# User_IO_Buffers.net
KiCad netlist of a schematic drawn in Altium Designer
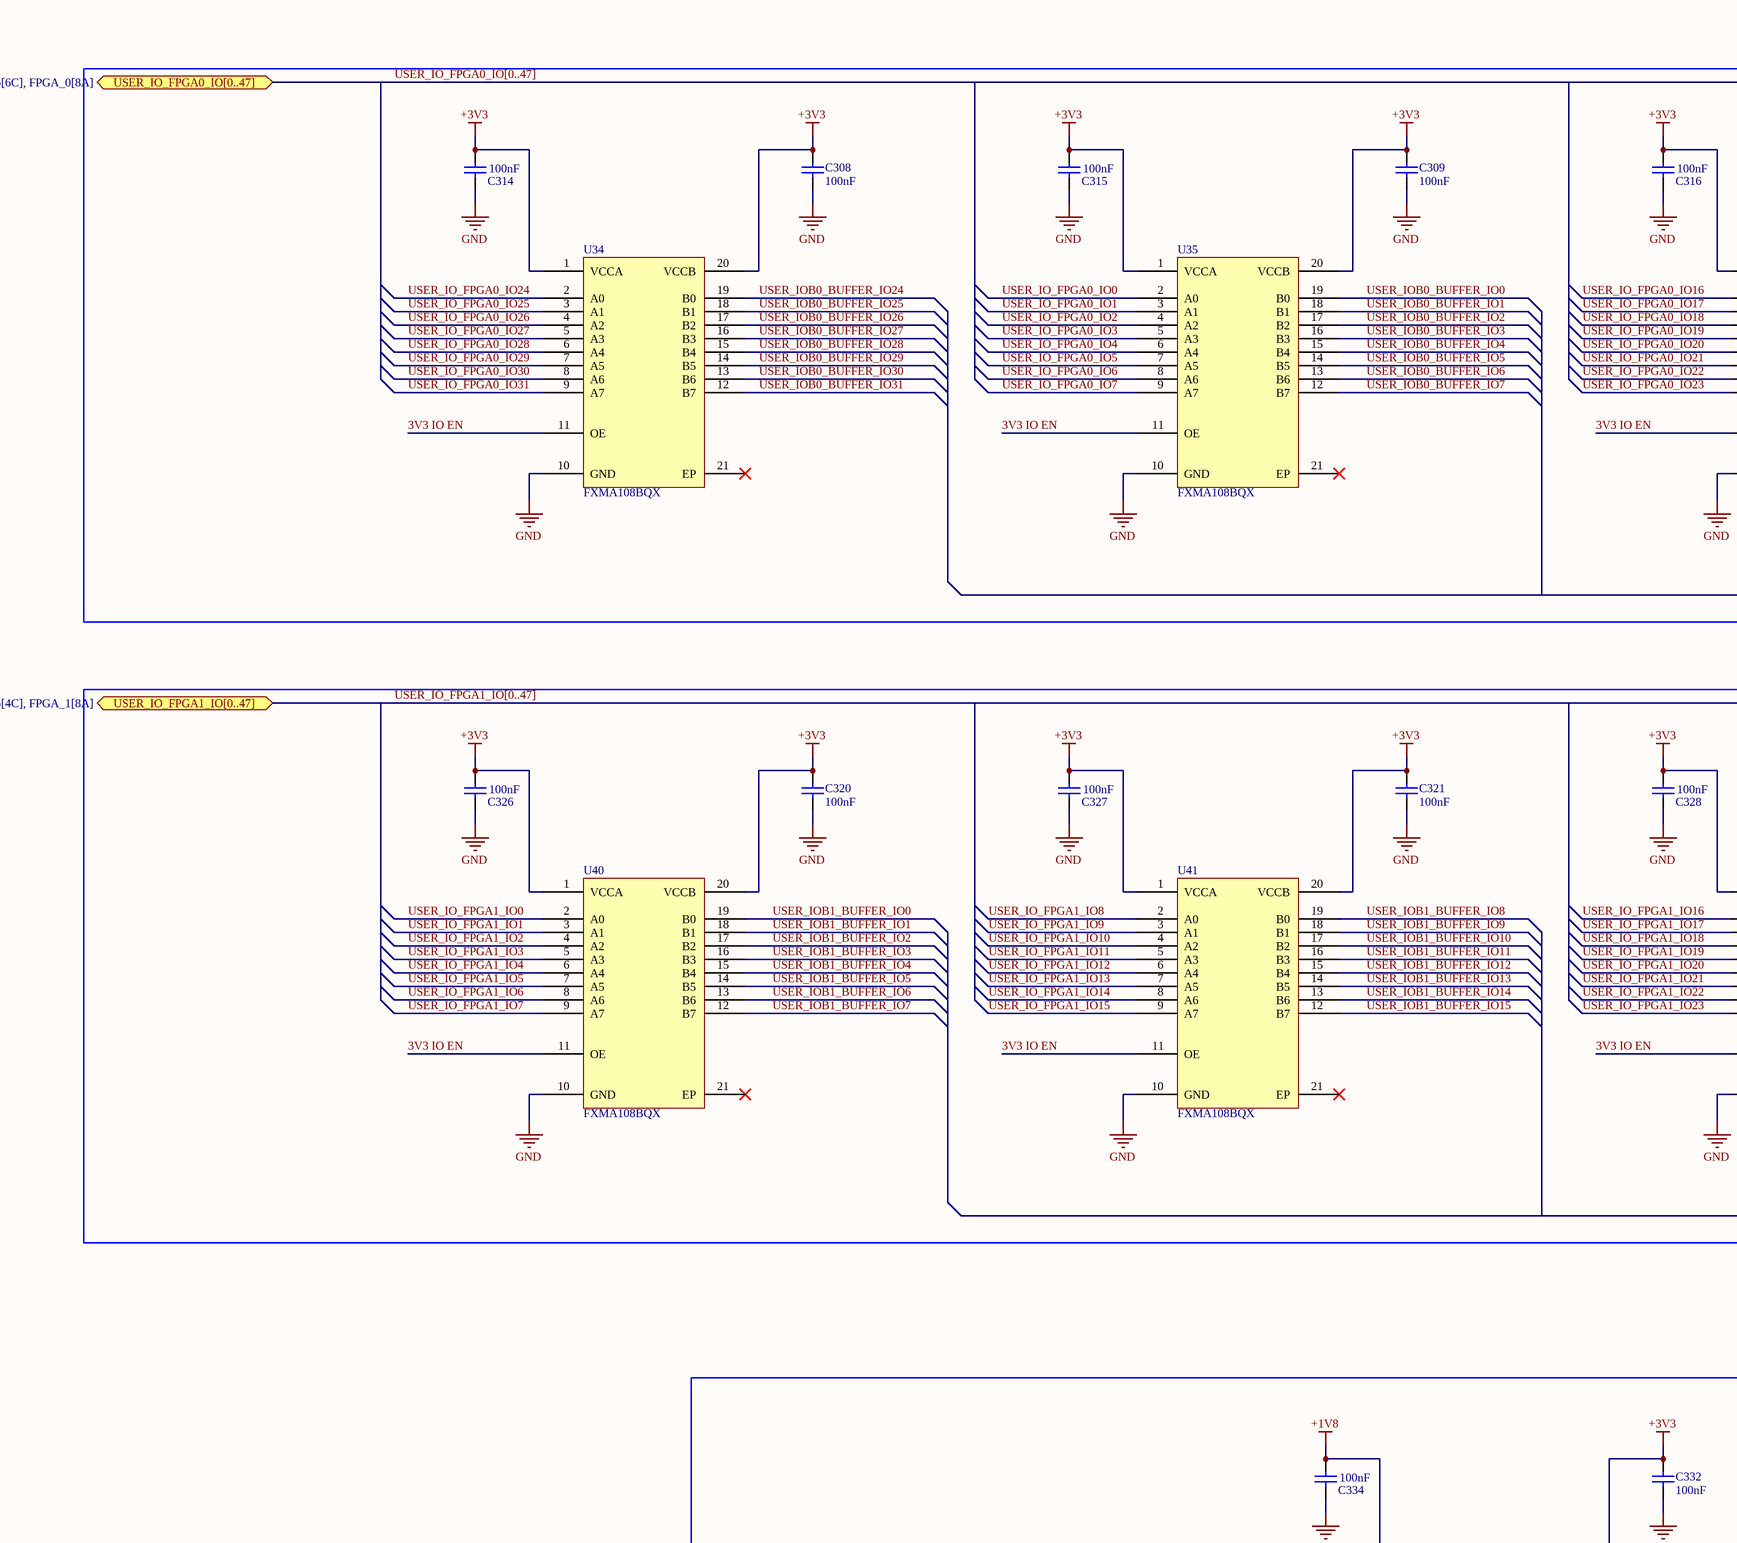
[diagram p0: User IO Buffers.SchDoc, top left]
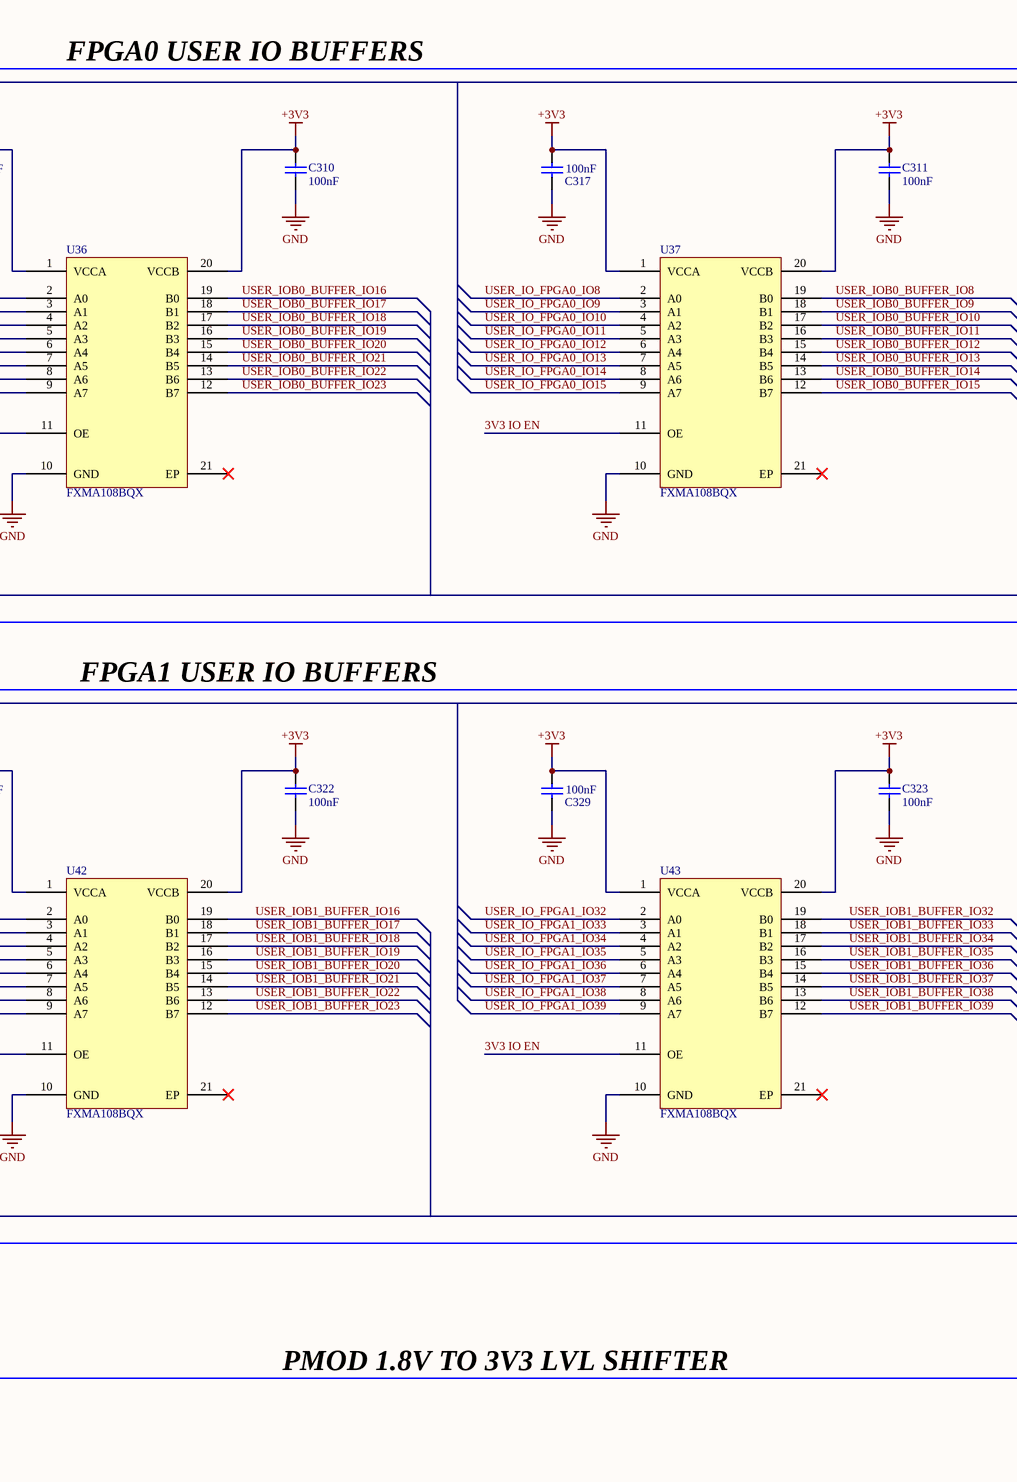
[diagram p1: User IO Buffers.SchDoc, top middle]
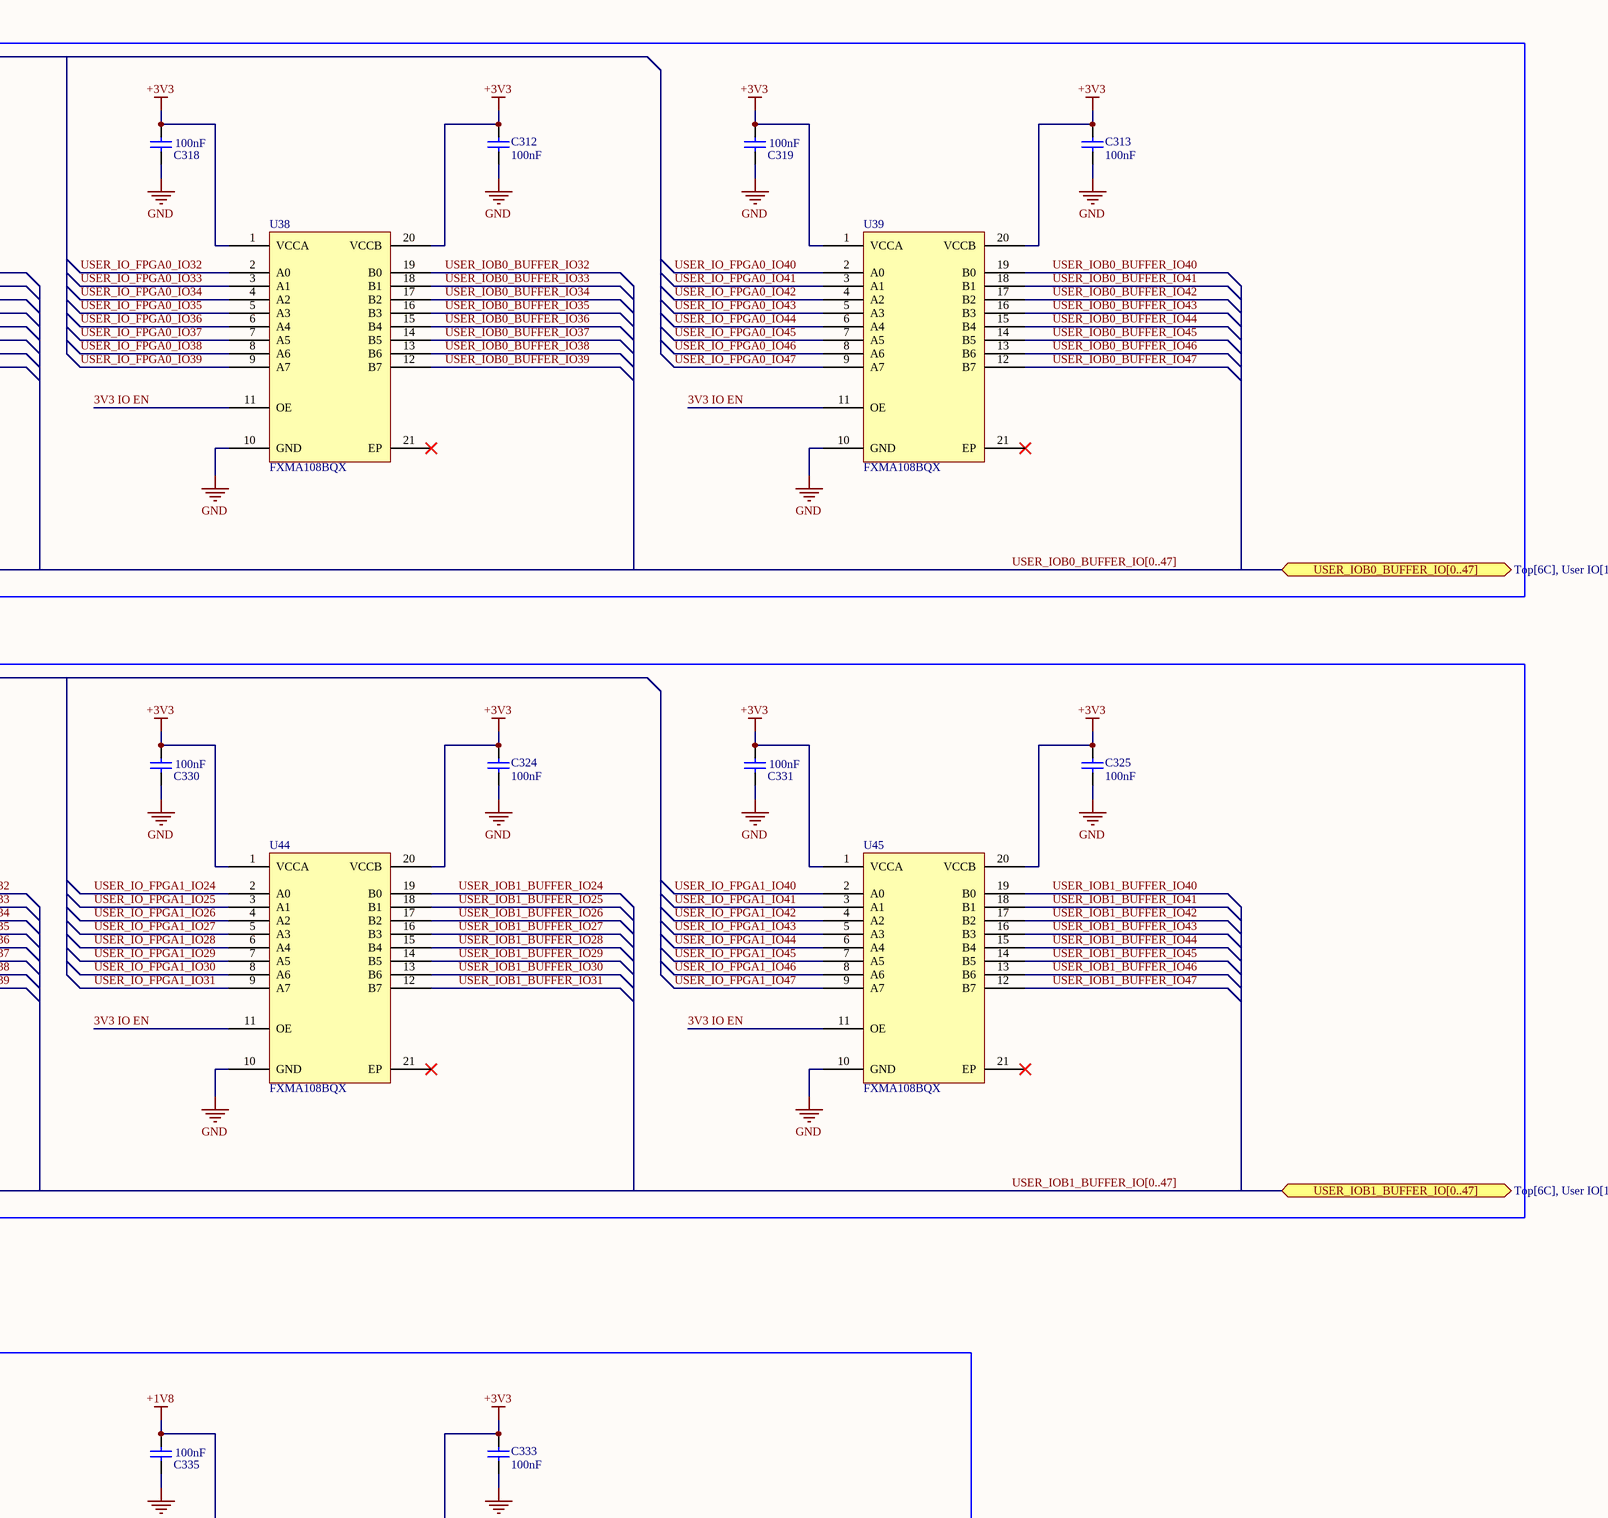
[diagram p2: User IO Buffers.SchDoc, top right]
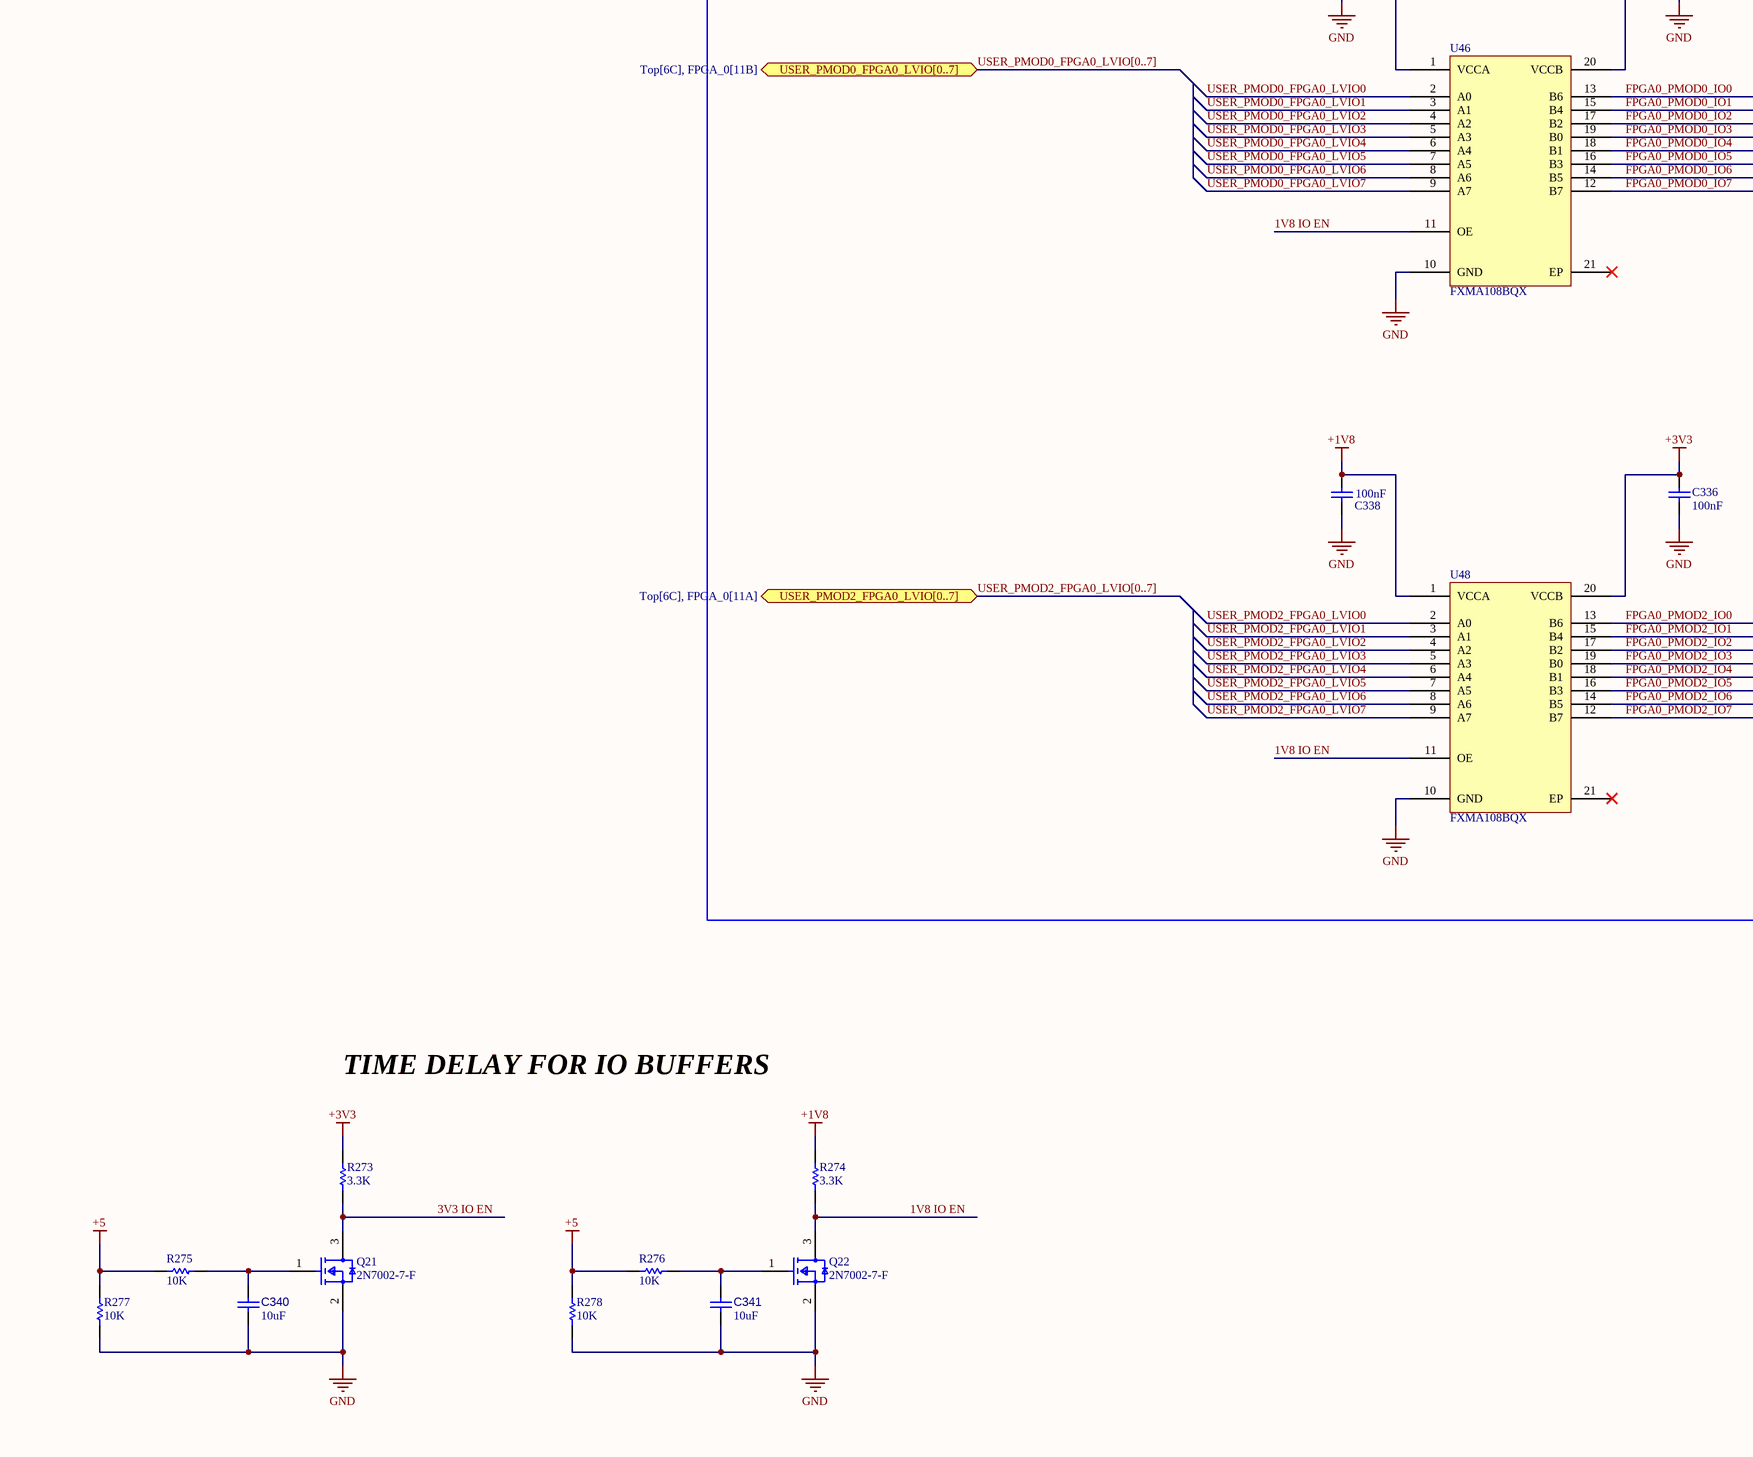
[diagram p3: User IO Buffers.SchDoc, bottom left]
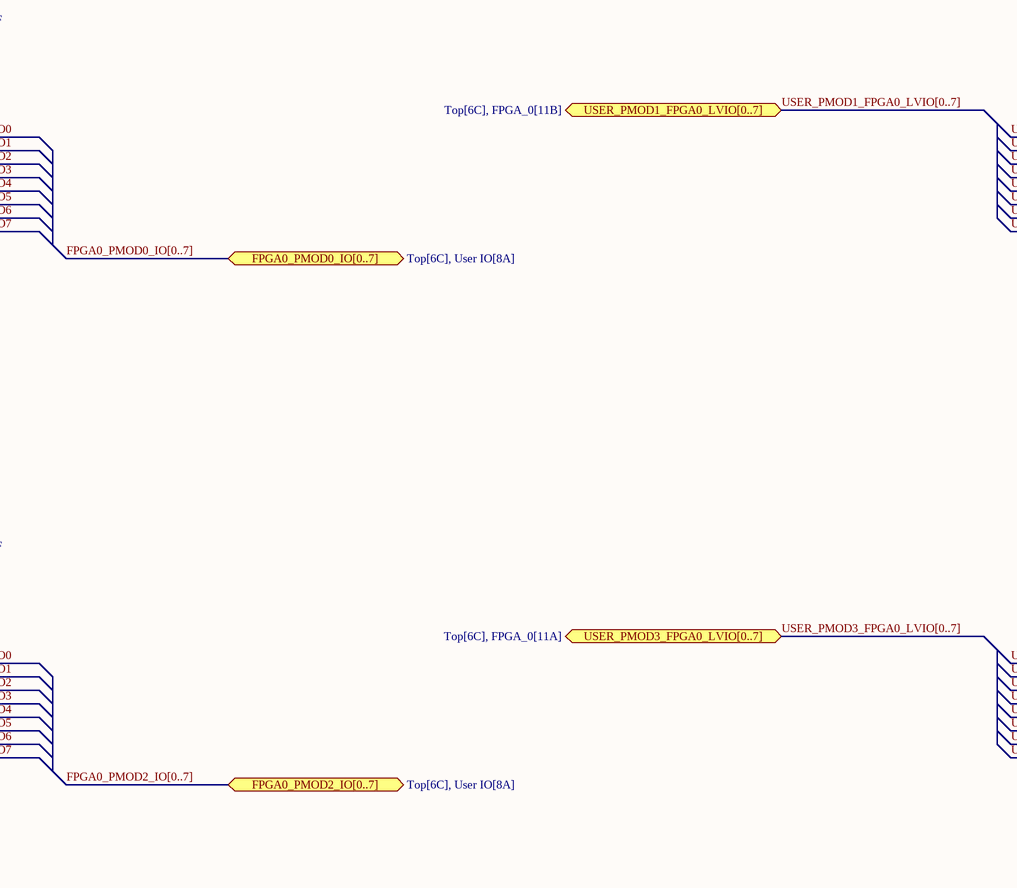
[diagram p4: User IO Buffers.SchDoc, bottom middle]
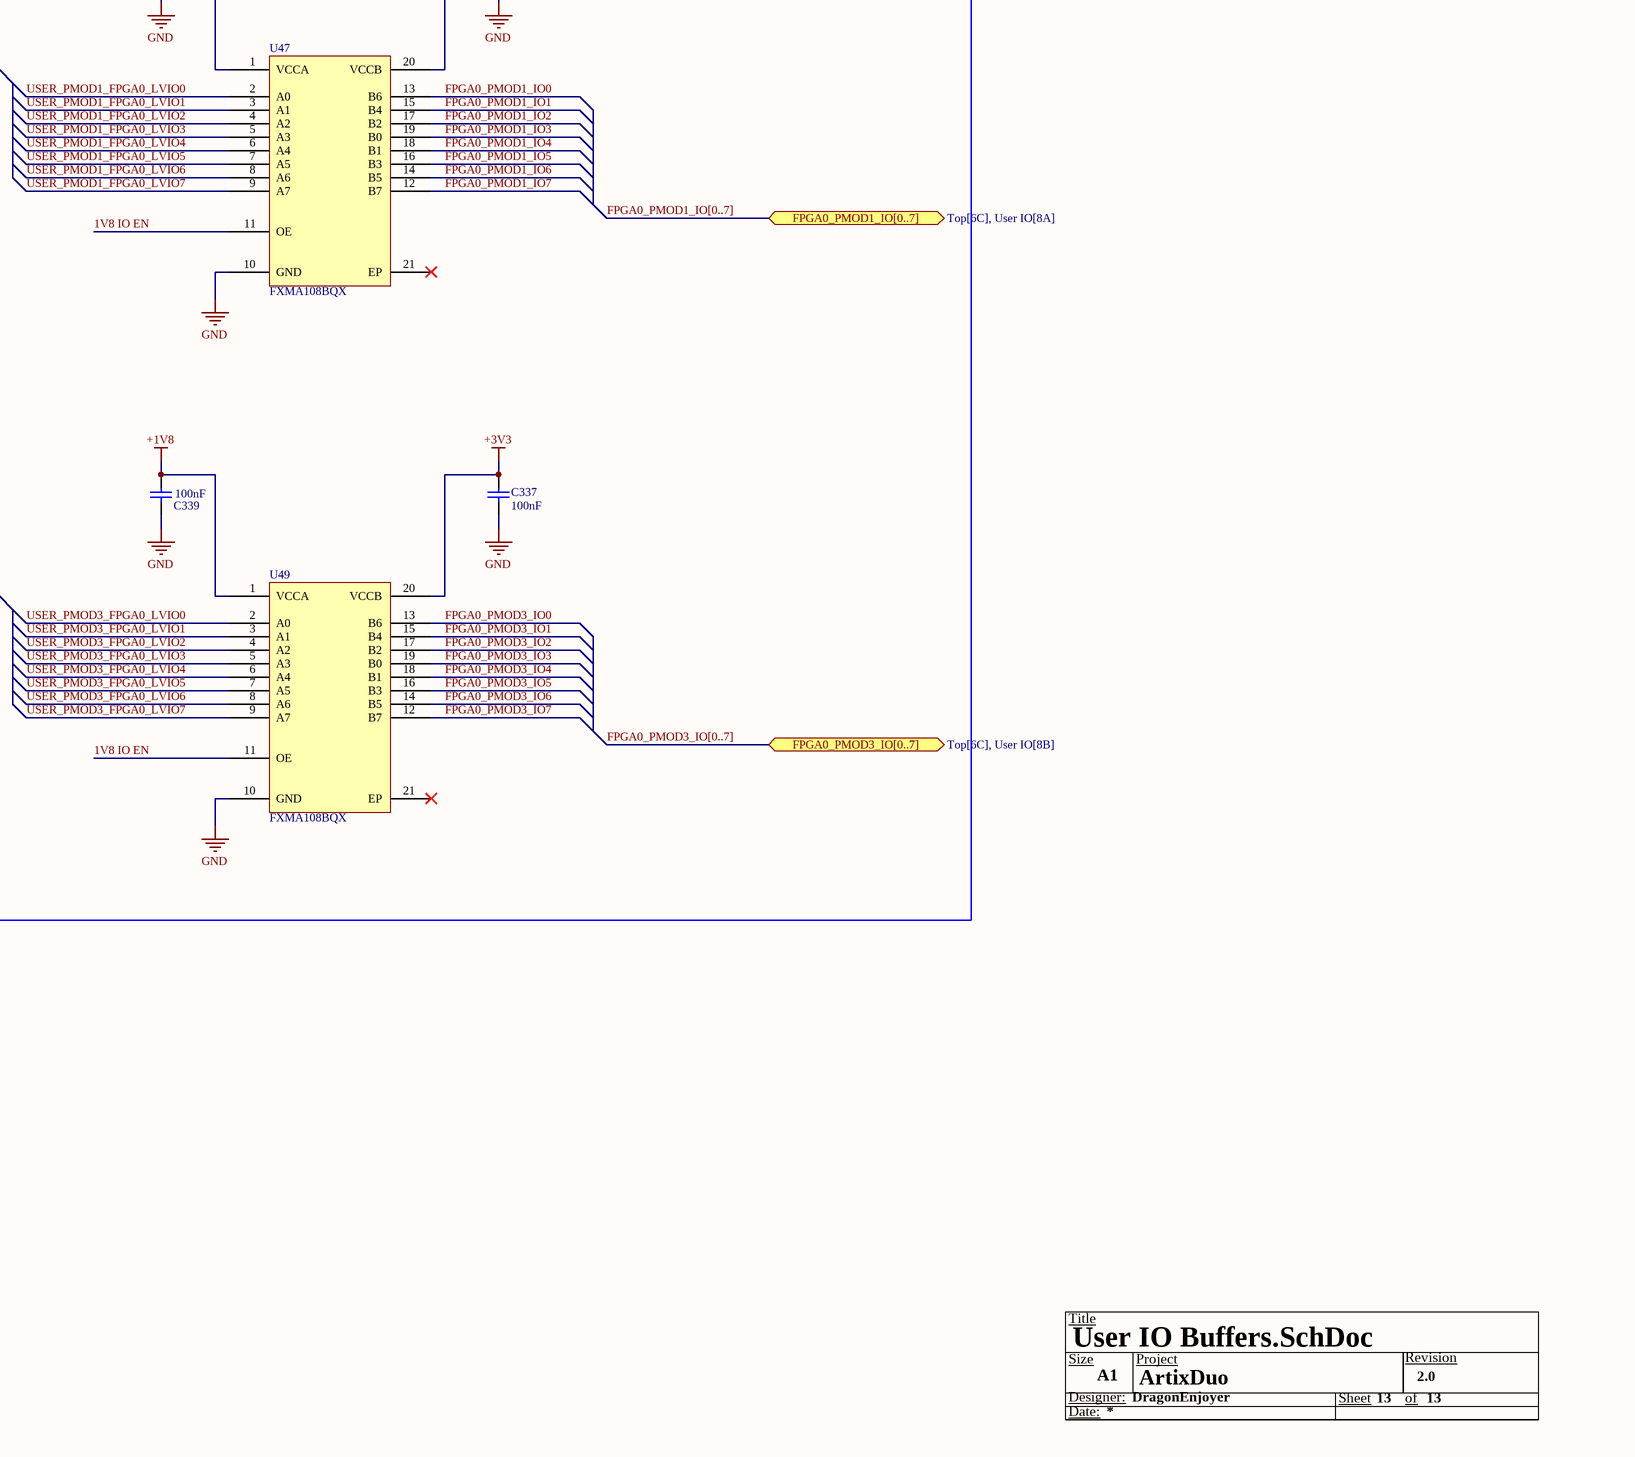
[diagram p5: User IO Buffers.SchDoc, bottom right]

(export (version "E")
  (design (tool "Eeschema 10.0.6"))
  (components
    (comp (ref "C308")
      (value "100nF")
      (footprint "CAPC1005X05N")
      (description "Cap Ceramic 0.1uF 50V X7R 20% SMD 0402 125°C Paper T/R GRM155R71H104ME14J")
      (fields (field (name "VOLTAGE") "50V"))
      (libsource (lib "Main Workspace") (part "CAP"))
    )
    (comp (ref "C309")
      (value "100nF")
      (footprint "CAPC1005X05N")
      (description "Cap Ceramic 0.1uF 50V X7R 20% SMD 0402 125°C Paper T/R GRM155R71H104ME14J")
      (fields (field (name "VOLTAGE") "50V"))
      (libsource (lib "Main Workspace") (part "CAP"))
    )
    (comp (ref "C310")
      (value "100nF")
      (footprint "CAPC1005X05N")
      (description "Cap Ceramic 0.1uF 50V X7R 20% SMD 0402 125°C Paper T/R GRM155R71H104ME14J")
      (fields (field (name "VOLTAGE") "50V"))
      (libsource (lib "Main Workspace") (part "CAP"))
    )
    (comp (ref "C311")
      (value "100nF")
      (footprint "CAPC1005X05N")
      (description "Cap Ceramic 0.1uF 50V X7R 20% SMD 0402 125°C Paper T/R GRM155R71H104ME14J")
      (fields (field (name "VOLTAGE") "50V"))
      (libsource (lib "Main Workspace") (part "CAP"))
    )
    (comp (ref "C312")
      (value "100nF")
      (footprint "CAPC1005X05N")
      (description "Cap Ceramic 0.1uF 50V X7R 20% SMD 0402 125°C Paper T/R GRM155R71H104ME14J")
      (fields (field (name "VOLTAGE") "50V"))
      (libsource (lib "Main Workspace") (part "CAP"))
    )
    (comp (ref "C313")
      (value "100nF")
      (footprint "CAPC1005X05N")
      (description "Cap Ceramic 0.1uF 50V X7R 20% SMD 0402 125°C Paper T/R GRM155R71H104ME14J")
      (fields (field (name "VOLTAGE") "50V"))
      (libsource (lib "Main Workspace") (part "CAP"))
    )
    (comp (ref "C314")
      (value "100nF")
      (footprint "CAPC1005X05N")
      (description "Cap Ceramic 0.1uF 50V X7R 20% SMD 0402 125°C Paper T/R GRM155R71H104ME14J")
      (fields (field (name "VOLTAGE") "50V"))
      (libsource (lib "Main Workspace") (part "CAP"))
    )
    (comp (ref "C315")
      (value "100nF")
      (footprint "CAPC1005X05N")
      (description "Cap Ceramic 0.1uF 50V X7R 20% SMD 0402 125°C Paper T/R GRM155R71H104ME14J")
      (fields (field (name "VOLTAGE") "50V"))
      (libsource (lib "Main Workspace") (part "CAP"))
    )
    (comp (ref "C316")
      (value "100nF")
      (footprint "CAPC1005X05N")
      (description "Cap Ceramic 0.1uF 50V X7R 20% SMD 0402 125°C Paper T/R GRM155R71H104ME14J")
      (fields (field (name "VOLTAGE") "50V"))
      (libsource (lib "Main Workspace") (part "CAP"))
    )
    (comp (ref "C317")
      (value "100nF")
      (footprint "CAPC1005X05N")
      (description "Cap Ceramic 0.1uF 50V X7R 20% SMD 0402 125°C Paper T/R GRM155R71H104ME14J")
      (fields (field (name "VOLTAGE") "50V"))
      (libsource (lib "Main Workspace") (part "CAP"))
    )
    (comp (ref "C318")
      (value "100nF")
      (footprint "CAPC1005X05N")
      (description "Cap Ceramic 0.1uF 50V X7R 20% SMD 0402 125°C Paper T/R GRM155R71H104ME14J")
      (fields (field (name "VOLTAGE") "50V"))
      (libsource (lib "Main Workspace") (part "CAP"))
    )
    (comp (ref "C319")
      (value "100nF")
      (footprint "CAPC1005X05N")
      (description "Cap Ceramic 0.1uF 50V X7R 20% SMD 0402 125°C Paper T/R GRM155R71H104ME14J")
      (fields (field (name "VOLTAGE") "50V"))
      (libsource (lib "Main Workspace") (part "CAP"))
    )
    (comp (ref "C320")
      (value "100nF")
      (footprint "CAPC1005X05N")
      (description "Cap Ceramic 0.1uF 50V X7R 20% SMD 0402 125°C Paper T/R GRM155R71H104ME14J")
      (fields (field (name "VOLTAGE") "50V"))
      (libsource (lib "Main Workspace") (part "CAP"))
    )
    (comp (ref "C321")
      (value "100nF")
      (footprint "CAPC1005X05N")
      (description "Cap Ceramic 0.1uF 50V X7R 20% SMD 0402 125°C Paper T/R GRM155R71H104ME14J")
      (fields (field (name "VOLTAGE") "50V"))
      (libsource (lib "Main Workspace") (part "CAP"))
    )
    (comp (ref "C322")
      (value "100nF")
      (footprint "CAPC1005X05N")
      (description "Cap Ceramic 0.1uF 50V X7R 20% SMD 0402 125°C Paper T/R GRM155R71H104ME14J")
      (fields (field (name "VOLTAGE") "50V"))
      (libsource (lib "Main Workspace") (part "CAP"))
    )
    (comp (ref "C323")
      (value "100nF")
      (footprint "CAPC1005X05N")
      (description "Cap Ceramic 0.1uF 50V X7R 20% SMD 0402 125°C Paper T/R GRM155R71H104ME14J")
      (fields (field (name "VOLTAGE") "50V"))
      (libsource (lib "Main Workspace") (part "CAP"))
    )
    (comp (ref "C324")
      (value "100nF")
      (footprint "CAPC1005X05N")
      (description "Cap Ceramic 0.1uF 50V X7R 20% SMD 0402 125°C Paper T/R GRM155R71H104ME14J")
      (fields (field (name "VOLTAGE") "50V"))
      (libsource (lib "Main Workspace") (part "CAP"))
    )
    (comp (ref "C325")
      (value "100nF")
      (footprint "CAPC1005X05N")
      (description "Cap Ceramic 0.1uF 50V X7R 20% SMD 0402 125°C Paper T/R GRM155R71H104ME14J")
      (fields (field (name "VOLTAGE") "50V"))
      (libsource (lib "Main Workspace") (part "CAP"))
    )
    (comp (ref "C326")
      (value "100nF")
      (footprint "CAPC1005X05N")
      (description "Cap Ceramic 0.1uF 50V X7R 20% SMD 0402 125°C Paper T/R GRM155R71H104ME14J")
      (fields (field (name "VOLTAGE") "50V"))
      (libsource (lib "Main Workspace") (part "CAP"))
    )
    (comp (ref "C327")
      (value "100nF")
      (footprint "CAPC1005X05N")
      (description "Cap Ceramic 0.1uF 50V X7R 20% SMD 0402 125°C Paper T/R GRM155R71H104ME14J")
      (fields (field (name "VOLTAGE") "50V"))
      (libsource (lib "Main Workspace") (part "CAP"))
    )
    (comp (ref "C328")
      (value "100nF")
      (footprint "CAPC1005X05N")
      (description "Cap Ceramic 0.1uF 50V X7R 20% SMD 0402 125°C Paper T/R GRM155R71H104ME14J")
      (fields (field (name "VOLTAGE") "50V"))
      (libsource (lib "Main Workspace") (part "CAP"))
    )
    (comp (ref "C329")
      (value "100nF")
      (footprint "CAPC1005X05N")
      (description "Cap Ceramic 0.1uF 50V X7R 20% SMD 0402 125°C Paper T/R GRM155R71H104ME14J")
      (fields (field (name "VOLTAGE") "50V"))
      (libsource (lib "Main Workspace") (part "CAP"))
    )
    (comp (ref "C330")
      (value "100nF")
      (footprint "CAPC1005X05N")
      (description "Cap Ceramic 0.1uF 50V X7R 20% SMD 0402 125°C Paper T/R GRM155R71H104ME14J")
      (fields (field (name "VOLTAGE") "50V"))
      (libsource (lib "Main Workspace") (part "CAP"))
    )
    (comp (ref "C331")
      (value "100nF")
      (footprint "CAPC1005X05N")
      (description "Cap Ceramic 0.1uF 50V X7R 20% SMD 0402 125°C Paper T/R GRM155R71H104ME14J")
      (fields (field (name "VOLTAGE") "50V"))
      (libsource (lib "Main Workspace") (part "CAP"))
    )
    (comp (ref "C332")
      (value "100nF")
      (footprint "CAPC1005X05N")
      (description "Cap Ceramic 0.1uF 50V X7R 20% SMD 0402 125°C Paper T/R GRM155R71H104ME14J")
      (fields (field (name "VOLTAGE") "50V"))
      (libsource (lib "Main Workspace") (part "CAP"))
    )
    (comp (ref "C333")
      (value "100nF")
      (footprint "CAPC1005X05N")
      (description "Cap Ceramic 0.1uF 50V X7R 20% SMD 0402 125°C Paper T/R GRM155R71H104ME14J")
      (fields (field (name "VOLTAGE") "50V"))
      (libsource (lib "Main Workspace") (part "CAP"))
    )
    (comp (ref "C334")
      (value "100nF")
      (footprint "CAPC1005X05N")
      (description "Cap Ceramic 0.1uF 50V X7R 20% SMD 0402 125°C Paper T/R GRM155R71H104ME14J")
      (fields (field (name "VOLTAGE") "50V"))
      (libsource (lib "Main Workspace") (part "CAP"))
    )
    (comp (ref "C335")
      (value "100nF")
      (footprint "CAPC1005X05N")
      (description "Cap Ceramic 0.1uF 50V X7R 20% SMD 0402 125°C Paper T/R GRM155R71H104ME14J")
      (fields (field (name "VOLTAGE") "50V"))
      (libsource (lib "Main Workspace") (part "CAP"))
    )
    (comp (ref "C336")
      (value "100nF")
      (footprint "CAPC1005X05N")
      (description "Cap Ceramic 0.1uF 50V X7R 20% SMD 0402 125°C Paper T/R GRM155R71H104ME14J")
      (fields (field (name "VOLTAGE") "50V"))
      (libsource (lib "Main Workspace") (part "CAP"))
    )
    (comp (ref "C337")
      (value "100nF")
      (footprint "CAPC1005X05N")
      (description "Cap Ceramic 0.1uF 50V X7R 20% SMD 0402 125°C Paper T/R GRM155R71H104ME14J")
      (fields (field (name "VOLTAGE") "50V"))
      (libsource (lib "Main Workspace") (part "CAP"))
    )
    (comp (ref "C338")
      (value "100nF")
      (footprint "CAPC1005X05N")
      (description "Cap Ceramic 0.1uF 50V X7R 20% SMD 0402 125°C Paper T/R GRM155R71H104ME14J")
      (fields (field (name "VOLTAGE") "50V"))
      (libsource (lib "Main Workspace") (part "CAP"))
    )
    (comp (ref "C339")
      (value "100nF")
      (footprint "CAPC1005X05N")
      (description "Cap Ceramic 0.1uF 50V X7R 20% SMD 0402 125°C Paper T/R GRM155R71H104ME14J")
      (fields (field (name "VOLTAGE") "50V"))
      (libsource (lib "Main Workspace") (part "CAP"))
    )
    (comp (ref "C340")
      (value "10uF")
      (footprint "CAPC1608X04N")
      (description "CAP CER 10UF 25V X5R 0603")
      (fields (field (name "VOLTAGE") "25V") (field (name "TOLERANCE") "20%"))
      (libsource (lib "Main Workspace") (part "CAP-NP-2"))
    )
    (comp (ref "C341")
      (value "10uF")
      (footprint "CAPC1608X04N")
      (description "CAP CER 10UF 25V X5R 0603")
      (fields (field (name "VOLTAGE") "25V") (field (name "TOLERANCE") "20%"))
      (libsource (lib "Main Workspace") (part "CAP-NP-2"))
    )
    (comp (ref "Q21")
      (value "2N7002-7-F")
      (footprint "FP-SOT23-MFG")
      (description "MOSFET N-CH 60V 115MA SOT23-3")
      (fields (field (name "VOLTAGE") "60V"))
      (libsource (lib "Altium Content Vault") (part "3b9c635fedb024a5347a57b145af9cc"))
    )
    (comp (ref "Q22")
      (value "2N7002-7-F")
      (footprint "FP-SOT23-MFG")
      (description "MOSFET N-CH 60V 115MA SOT23-3")
      (fields (field (name "VOLTAGE") "60V"))
      (libsource (lib "Altium Content Vault") (part "3b9c635fedb024a5347a57b145af9cc"))
    )
    (comp (ref "R273")
      (value "3.3K")
      (footprint "RESC1005X40X25NL05T10")
      (description "CRCW04023K30FKEDHP")
      (fields (field (name "MANUFACTURER") "Vishay Dale"))
      (libsource (lib "Altium Content Vault") (part "RES"))
    )
    (comp (ref "R274")
      (value "3.3K")
      (footprint "RESC1005X40X25NL05T10")
      (description "CRCW04023K30FKEDHP")
      (fields (field (name "MANUFACTURER") "Vishay Dale"))
      (libsource (lib "Altium Content Vault") (part "RES"))
    )
    (comp (ref "R275")
      (value "10K")
      (footprint "RESC1005X40X25NL05T10")
      (description "RC0402FR-0710KL")
      (fields (field (name "MANUFACTURER") "Yageo / Phycomp"))
      (libsource (lib "Altium Content Vault") (part "RES"))
    )
    (comp (ref "R276")
      (value "10K")
      (footprint "RESC1005X40X25NL05T10")
      (description "RC0402FR-0710KL")
      (fields (field (name "MANUFACTURER") "Yageo / Phycomp"))
      (libsource (lib "Altium Content Vault") (part "RES"))
    )
    (comp (ref "R277")
      (value "10K")
      (footprint "RESC1005X40X25NL05T10")
      (description "RC0402FR-0710KL")
      (fields (field (name "MANUFACTURER") "Yageo / Phycomp"))
      (libsource (lib "Altium Content Vault") (part "RES"))
    )
    (comp (ref "R278")
      (value "10K")
      (footprint "RESC1005X40X25NL05T10")
      (description "RC0402FR-0710KL")
      (fields (field (name "MANUFACTURER") "Yageo / Phycomp"))
      (libsource (lib "Altium Content Vault") (part "RES"))
    )
    (comp (ref "U34")
      (value "FXMA108BQX")
      (footprint "QFN50P450X250X80_HS-21N")
      (description "FXMA108 Series 3.6 V Surface Mount Dual Supply 8-Bit Voltage Translator -DQFN-20")
      (libsource (lib "Main Workspace") (part "FXMA108BQX"))
    )
    (comp (ref "U35")
      (value "FXMA108BQX")
      (footprint "QFN50P450X250X80_HS-21N")
      (description "FXMA108 Series 3.6 V Surface Mount Dual Supply 8-Bit Voltage Translator -DQFN-20")
      (libsource (lib "Main Workspace") (part "FXMA108BQX"))
    )
    (comp (ref "U36")
      (value "FXMA108BQX")
      (footprint "QFN50P450X250X80_HS-21N")
      (description "FXMA108 Series 3.6 V Surface Mount Dual Supply 8-Bit Voltage Translator -DQFN-20")
      (libsource (lib "Main Workspace") (part "FXMA108BQX"))
    )
    (comp (ref "U37")
      (value "FXMA108BQX")
      (footprint "QFN50P450X250X80_HS-21N")
      (description "FXMA108 Series 3.6 V Surface Mount Dual Supply 8-Bit Voltage Translator -DQFN-20")
      (libsource (lib "Main Workspace") (part "FXMA108BQX"))
    )
    (comp (ref "U38")
      (value "FXMA108BQX")
      (footprint "QFN50P450X250X80_HS-21N")
      (description "FXMA108 Series 3.6 V Surface Mount Dual Supply 8-Bit Voltage Translator -DQFN-20")
      (libsource (lib "Main Workspace") (part "FXMA108BQX"))
    )
    (comp (ref "U39")
      (value "FXMA108BQX")
      (footprint "QFN50P450X250X80_HS-21N")
      (description "FXMA108 Series 3.6 V Surface Mount Dual Supply 8-Bit Voltage Translator -DQFN-20")
      (libsource (lib "Main Workspace") (part "FXMA108BQX"))
    )
    (comp (ref "U40")
      (value "FXMA108BQX")
      (footprint "QFN50P450X250X80_HS-21N")
      (description "FXMA108 Series 3.6 V Surface Mount Dual Supply 8-Bit Voltage Translator -DQFN-20")
      (libsource (lib "Main Workspace") (part "FXMA108BQX"))
    )
    (comp (ref "U41")
      (value "FXMA108BQX")
      (footprint "QFN50P450X250X80_HS-21N")
      (description "FXMA108 Series 3.6 V Surface Mount Dual Supply 8-Bit Voltage Translator -DQFN-20")
      (libsource (lib "Main Workspace") (part "FXMA108BQX"))
    )
    (comp (ref "U42")
      (value "FXMA108BQX")
      (footprint "QFN50P450X250X80_HS-21N")
      (description "FXMA108 Series 3.6 V Surface Mount Dual Supply 8-Bit Voltage Translator -DQFN-20")
      (libsource (lib "Main Workspace") (part "FXMA108BQX"))
    )
    (comp (ref "U43")
      (value "FXMA108BQX")
      (footprint "QFN50P450X250X80_HS-21N")
      (description "FXMA108 Series 3.6 V Surface Mount Dual Supply 8-Bit Voltage Translator -DQFN-20")
      (libsource (lib "Main Workspace") (part "FXMA108BQX"))
    )
    (comp (ref "U44")
      (value "FXMA108BQX")
      (footprint "QFN50P450X250X80_HS-21N")
      (description "FXMA108 Series 3.6 V Surface Mount Dual Supply 8-Bit Voltage Translator -DQFN-20")
      (libsource (lib "Main Workspace") (part "FXMA108BQX"))
    )
    (comp (ref "U45")
      (value "FXMA108BQX")
      (footprint "QFN50P450X250X80_HS-21N")
      (description "FXMA108 Series 3.6 V Surface Mount Dual Supply 8-Bit Voltage Translator -DQFN-20")
      (libsource (lib "Main Workspace") (part "FXMA108BQX"))
    )
    (comp (ref "U46")
      (value "FXMA108BQX")
      (footprint "QFN50P450X250X80_HS-21N")
      (description "FXMA108 Series 3.6 V Surface Mount Dual Supply 8-Bit Voltage Translator -DQFN-20")
      (libsource (lib "") (part "FXMA108BQX_1"))
    )
    (comp (ref "U47")
      (value "FXMA108BQX")
      (footprint "QFN50P450X250X80_HS-21N")
      (description "FXMA108 Series 3.6 V Surface Mount Dual Supply 8-Bit Voltage Translator -DQFN-20")
      (libsource (lib "") (part "FXMA108BQX_1"))
    )
    (comp (ref "U48")
      (value "FXMA108BQX")
      (footprint "QFN50P450X250X80_HS-21N")
      (description "FXMA108 Series 3.6 V Surface Mount Dual Supply 8-Bit Voltage Translator -DQFN-20")
      (libsource (lib "") (part "FXMA108BQX_1"))
    )
    (comp (ref "U49")
      (value "FXMA108BQX")
      (footprint "QFN50P450X250X80_HS-21N")
      (description "FXMA108 Series 3.6 V Surface Mount Dual Supply 8-Bit Voltage Translator -DQFN-20")
      (libsource (lib "") (part "FXMA108BQX_1"))
    )
  )
  (nets
    (net (code "1") (name "+1V8") (class "Default")
      (node (ref "C334") (pin "2") (pinfunction "2_2") (pintype "passive"))
      (node (ref "C335") (pin "2") (pinfunction "2_2") (pintype "passive"))
      (node (ref "C338") (pin "2") (pinfunction "2_2") (pintype "passive"))
      (node (ref "C339") (pin "2") (pinfunction "2_2") (pintype "passive"))
      (node (ref "R274") (pin "2") (pinfunction "2_2") (pintype "passive"))
      (node (ref "U46") (pin "1") (pinfunction "VCCA_1") (pintype "passive"))
      (node (ref "U47") (pin "1") (pinfunction "VCCA_1") (pintype "passive"))
      (node (ref "U48") (pin "1") (pinfunction "VCCA_1") (pintype "passive"))
      (node (ref "U49") (pin "1") (pinfunction "VCCA_1") (pintype "passive"))
    )
    (net (code "2") (name "+3V3") (class "Default")
      (node (ref "C308") (pin "2") (pinfunction "2_2") (pintype "passive"))
      (node (ref "C309") (pin "2") (pinfunction "2_2") (pintype "passive"))
      (node (ref "C310") (pin "2") (pinfunction "2_2") (pintype "passive"))
      (node (ref "C311") (pin "2") (pinfunction "2_2") (pintype "passive"))
      (node (ref "C312") (pin "2") (pinfunction "2_2") (pintype "passive"))
      (node (ref "C313") (pin "2") (pinfunction "2_2") (pintype "passive"))
      (node (ref "C314") (pin "2") (pinfunction "2_2") (pintype "passive"))
      (node (ref "C315") (pin "2") (pinfunction "2_2") (pintype "passive"))
      (node (ref "C316") (pin "2") (pinfunction "2_2") (pintype "passive"))
      (node (ref "C317") (pin "2") (pinfunction "2_2") (pintype "passive"))
      (node (ref "C318") (pin "2") (pinfunction "2_2") (pintype "passive"))
      (node (ref "C319") (pin "2") (pinfunction "2_2") (pintype "passive"))
      (node (ref "C320") (pin "2") (pinfunction "2_2") (pintype "passive"))
      (node (ref "C321") (pin "2") (pinfunction "2_2") (pintype "passive"))
      (node (ref "C322") (pin "2") (pinfunction "2_2") (pintype "passive"))
      (node (ref "C323") (pin "2") (pinfunction "2_2") (pintype "passive"))
      (node (ref "C324") (pin "2") (pinfunction "2_2") (pintype "passive"))
      (node (ref "C325") (pin "2") (pinfunction "2_2") (pintype "passive"))
      (node (ref "C326") (pin "2") (pinfunction "2_2") (pintype "passive"))
      (node (ref "C327") (pin "2") (pinfunction "2_2") (pintype "passive"))
      (node (ref "C328") (pin "2") (pinfunction "2_2") (pintype "passive"))
      (node (ref "C329") (pin "2") (pinfunction "2_2") (pintype "passive"))
      (node (ref "C330") (pin "2") (pinfunction "2_2") (pintype "passive"))
      (node (ref "C331") (pin "2") (pinfunction "2_2") (pintype "passive"))
      (node (ref "C332") (pin "2") (pinfunction "2_2") (pintype "passive"))
      (node (ref "C333") (pin "2") (pinfunction "2_2") (pintype "passive"))
      (node (ref "C336") (pin "2") (pinfunction "2_2") (pintype "passive"))
      (node (ref "C337") (pin "2") (pinfunction "2_2") (pintype "passive"))
      (node (ref "R273") (pin "2") (pinfunction "2_2") (pintype "passive"))
      (node (ref "U34") (pin "1") (pinfunction "VCCA_1") (pintype "passive"))
      (node (ref "U34") (pin "20") (pinfunction "VCCB_20") (pintype "passive"))
      (node (ref "U35") (pin "1") (pinfunction "VCCA_1") (pintype "passive"))
      (node (ref "U35") (pin "20") (pinfunction "VCCB_20") (pintype "passive"))
      (node (ref "U36") (pin "1") (pinfunction "VCCA_1") (pintype "passive"))
      (node (ref "U36") (pin "20") (pinfunction "VCCB_20") (pintype "passive"))
      (node (ref "U37") (pin "1") (pinfunction "VCCA_1") (pintype "passive"))
      (node (ref "U37") (pin "20") (pinfunction "VCCB_20") (pintype "passive"))
      (node (ref "U38") (pin "1") (pinfunction "VCCA_1") (pintype "passive"))
      (node (ref "U38") (pin "20") (pinfunction "VCCB_20") (pintype "passive"))
      (node (ref "U39") (pin "1") (pinfunction "VCCA_1") (pintype "passive"))
      (node (ref "U39") (pin "20") (pinfunction "VCCB_20") (pintype "passive"))
      (node (ref "U40") (pin "1") (pinfunction "VCCA_1") (pintype "passive"))
      (node (ref "U40") (pin "20") (pinfunction "VCCB_20") (pintype "passive"))
      (node (ref "U41") (pin "1") (pinfunction "VCCA_1") (pintype "passive"))
      (node (ref "U41") (pin "20") (pinfunction "VCCB_20") (pintype "passive"))
      (node (ref "U42") (pin "1") (pinfunction "VCCA_1") (pintype "passive"))
      (node (ref "U42") (pin "20") (pinfunction "VCCB_20") (pintype "passive"))
      (node (ref "U43") (pin "1") (pinfunction "VCCA_1") (pintype "passive"))
      (node (ref "U43") (pin "20") (pinfunction "VCCB_20") (pintype "passive"))
      (node (ref "U44") (pin "1") (pinfunction "VCCA_1") (pintype "passive"))
      (node (ref "U44") (pin "20") (pinfunction "VCCB_20") (pintype "passive"))
      (node (ref "U45") (pin "1") (pinfunction "VCCA_1") (pintype "passive"))
      (node (ref "U45") (pin "20") (pinfunction "VCCB_20") (pintype "passive"))
      (node (ref "U46") (pin "20") (pinfunction "VCCB_20") (pintype "passive"))
      (node (ref "U47") (pin "20") (pinfunction "VCCB_20") (pintype "passive"))
      (node (ref "U48") (pin "20") (pinfunction "VCCB_20") (pintype "passive"))
      (node (ref "U49") (pin "20") (pinfunction "VCCB_20") (pintype "passive"))
    )
    (net (code "3") (name "+5") (class "Default")
      (node (ref "R275") (pin "2") (pinfunction "2_2") (pintype "passive"))
      (node (ref "R276") (pin "2") (pinfunction "2_2") (pintype "passive"))
      (node (ref "R277") (pin "1") (pinfunction "1_1") (pintype "passive"))
      (node (ref "R278") (pin "1") (pinfunction "1_1") (pintype "passive"))
    )
    (net (code "4") (name "/1V8 IO EN") (class "Default")
      (node (ref "Q22") (pin "3") (pinfunction "D_3") (pintype "passive"))
      (node (ref "R274") (pin "1") (pinfunction "1_1") (pintype "passive"))
      (node (ref "U46") (pin "11") (pinfunction "OE_11") (pintype "passive"))
      (node (ref "U47") (pin "11") (pinfunction "OE_11") (pintype "passive"))
      (node (ref "U48") (pin "11") (pinfunction "OE_11") (pintype "passive"))
      (node (ref "U49") (pin "11") (pinfunction "OE_11") (pintype "passive"))
    )
    (net (code "5") (name "/3V3 IO EN") (class "Default")
      (node (ref "Q21") (pin "3") (pinfunction "D_3") (pintype "passive"))
      (node (ref "R273") (pin "1") (pinfunction "1_1") (pintype "passive"))
      (node (ref "U34") (pin "11") (pinfunction "OE_11") (pintype "passive"))
      (node (ref "U35") (pin "11") (pinfunction "OE_11") (pintype "passive"))
      (node (ref "U36") (pin "11") (pinfunction "OE_11") (pintype "passive"))
      (node (ref "U37") (pin "11") (pinfunction "OE_11") (pintype "passive"))
      (node (ref "U38") (pin "11") (pinfunction "OE_11") (pintype "passive"))
      (node (ref "U39") (pin "11") (pinfunction "OE_11") (pintype "passive"))
      (node (ref "U40") (pin "11") (pinfunction "OE_11") (pintype "passive"))
      (node (ref "U41") (pin "11") (pinfunction "OE_11") (pintype "passive"))
      (node (ref "U42") (pin "11") (pinfunction "OE_11") (pintype "passive"))
      (node (ref "U43") (pin "11") (pinfunction "OE_11") (pintype "passive"))
      (node (ref "U44") (pin "11") (pinfunction "OE_11") (pintype "passive"))
      (node (ref "U45") (pin "11") (pinfunction "OE_11") (pintype "passive"))
    )
    (net (code "6") (name "/FPGA0_PMOD0_IO0") (class "Default")
      (node (ref "U46") (pin "13") (pinfunction "B6_13") (pintype "passive"))
    )
    (net (code "7") (name "/FPGA0_PMOD0_IO1") (class "Default")
      (node (ref "U46") (pin "15") (pinfunction "B4_15") (pintype "passive"))
    )
    (net (code "8") (name "/FPGA0_PMOD0_IO2") (class "Default")
      (node (ref "U46") (pin "17") (pinfunction "B2_17") (pintype "passive"))
    )
    (net (code "9") (name "/FPGA0_PMOD0_IO3") (class "Default")
      (node (ref "U46") (pin "19") (pinfunction "B0_19") (pintype "passive"))
    )
    (net (code "10") (name "/FPGA0_PMOD0_IO4") (class "Default")
      (node (ref "U46") (pin "18") (pinfunction "B1_18") (pintype "passive"))
    )
    (net (code "11") (name "/FPGA0_PMOD0_IO5") (class "Default")
      (node (ref "U46") (pin "16") (pinfunction "B3_16") (pintype "passive"))
    )
    (net (code "12") (name "/FPGA0_PMOD0_IO6") (class "Default")
      (node (ref "U46") (pin "14") (pinfunction "B5_14") (pintype "passive"))
    )
    (net (code "13") (name "/FPGA0_PMOD0_IO7") (class "Default")
      (node (ref "U46") (pin "12") (pinfunction "B7_12") (pintype "passive"))
    )
    (net (code "15") (name "/FPGA0_PMOD1_IO0") (class "Default")
      (node (ref "U47") (pin "13") (pinfunction "B6_13") (pintype "passive"))
    )
    (net (code "16") (name "/FPGA0_PMOD1_IO1") (class "Default")
      (node (ref "U47") (pin "15") (pinfunction "B4_15") (pintype "passive"))
    )
    (net (code "17") (name "/FPGA0_PMOD1_IO2") (class "Default")
      (node (ref "U47") (pin "17") (pinfunction "B2_17") (pintype "passive"))
    )
    (net (code "18") (name "/FPGA0_PMOD1_IO3") (class "Default")
      (node (ref "U47") (pin "19") (pinfunction "B0_19") (pintype "passive"))
    )
    (net (code "19") (name "/FPGA0_PMOD1_IO4") (class "Default")
      (node (ref "U47") (pin "18") (pinfunction "B1_18") (pintype "passive"))
    )
    (net (code "20") (name "/FPGA0_PMOD1_IO5") (class "Default")
      (node (ref "U47") (pin "16") (pinfunction "B3_16") (pintype "passive"))
    )
    (net (code "21") (name "/FPGA0_PMOD1_IO6") (class "Default")
      (node (ref "U47") (pin "14") (pinfunction "B5_14") (pintype "passive"))
    )
    (net (code "22") (name "/FPGA0_PMOD1_IO7") (class "Default")
      (node (ref "U47") (pin "12") (pinfunction "B7_12") (pintype "passive"))
    )
    (net (code "24") (name "/FPGA0_PMOD2_IO0") (class "Default")
      (node (ref "U48") (pin "13") (pinfunction "B6_13") (pintype "passive"))
    )
    (net (code "25") (name "/FPGA0_PMOD2_IO1") (class "Default")
      (node (ref "U48") (pin "15") (pinfunction "B4_15") (pintype "passive"))
    )
    (net (code "26") (name "/FPGA0_PMOD2_IO2") (class "Default")
      (node (ref "U48") (pin "17") (pinfunction "B2_17") (pintype "passive"))
    )
    (net (code "27") (name "/FPGA0_PMOD2_IO3") (class "Default")
      (node (ref "U48") (pin "19") (pinfunction "B0_19") (pintype "passive"))
    )
    (net (code "28") (name "/FPGA0_PMOD2_IO4") (class "Default")
      (node (ref "U48") (pin "18") (pinfunction "B1_18") (pintype "passive"))
    )
    (net (code "29") (name "/FPGA0_PMOD2_IO5") (class "Default")
      (node (ref "U48") (pin "16") (pinfunction "B3_16") (pintype "passive"))
    )
    (net (code "30") (name "/FPGA0_PMOD2_IO6") (class "Default")
      (node (ref "U48") (pin "14") (pinfunction "B5_14") (pintype "passive"))
    )
    (net (code "31") (name "/FPGA0_PMOD2_IO7") (class "Default")
      (node (ref "U48") (pin "12") (pinfunction "B7_12") (pintype "passive"))
    )
    (net (code "33") (name "/FPGA0_PMOD3_IO0") (class "Default")
      (node (ref "U49") (pin "13") (pinfunction "B6_13") (pintype "passive"))
    )
    (net (code "34") (name "/FPGA0_PMOD3_IO1") (class "Default")
      (node (ref "U49") (pin "15") (pinfunction "B4_15") (pintype "passive"))
    )
    (net (code "35") (name "/FPGA0_PMOD3_IO2") (class "Default")
      (node (ref "U49") (pin "17") (pinfunction "B2_17") (pintype "passive"))
    )
    (net (code "36") (name "/FPGA0_PMOD3_IO3") (class "Default")
      (node (ref "U49") (pin "19") (pinfunction "B0_19") (pintype "passive"))
    )
    (net (code "37") (name "/FPGA0_PMOD3_IO4") (class "Default")
      (node (ref "U49") (pin "18") (pinfunction "B1_18") (pintype "passive"))
    )
    (net (code "38") (name "/FPGA0_PMOD3_IO5") (class "Default")
      (node (ref "U49") (pin "16") (pinfunction "B3_16") (pintype "passive"))
    )
    (net (code "39") (name "/FPGA0_PMOD3_IO6") (class "Default")
      (node (ref "U49") (pin "14") (pinfunction "B5_14") (pintype "passive"))
    )
    (net (code "40") (name "/FPGA0_PMOD3_IO7") (class "Default")
      (node (ref "U49") (pin "12") (pinfunction "B7_12") (pintype "passive"))
    )
    (net (code "42") (name "/USER_IOB0_BUFFER_IO0") (class "Default")
      (node (ref "U35") (pin "19") (pinfunction "B0_19") (pintype "passive"))
    )
    (net (code "43") (name "/USER_IOB0_BUFFER_IO1") (class "Default")
      (node (ref "U35") (pin "18") (pinfunction "B1_18") (pintype "passive"))
    )
    (net (code "44") (name "/USER_IOB0_BUFFER_IO2") (class "Default")
      (node (ref "U35") (pin "17") (pinfunction "B2_17") (pintype "passive"))
    )
    (net (code "45") (name "/USER_IOB0_BUFFER_IO3") (class "Default")
      (node (ref "U35") (pin "16") (pinfunction "B3_16") (pintype "passive"))
    )
    (net (code "46") (name "/USER_IOB0_BUFFER_IO4") (class "Default")
      (node (ref "U35") (pin "15") (pinfunction "B4_15") (pintype "passive"))
    )
    (net (code "47") (name "/USER_IOB0_BUFFER_IO5") (class "Default")
      (node (ref "U35") (pin "14") (pinfunction "B5_14") (pintype "passive"))
    )
    (net (code "48") (name "/USER_IOB0_BUFFER_IO6") (class "Default")
      (node (ref "U35") (pin "13") (pinfunction "B6_13") (pintype "passive"))
    )
    (net (code "49") (name "/USER_IOB0_BUFFER_IO7") (class "Default")
      (node (ref "U35") (pin "12") (pinfunction "B7_12") (pintype "passive"))
    )
    (net (code "50") (name "/USER_IOB0_BUFFER_IO8") (class "Default")
      (node (ref "U37") (pin "19") (pinfunction "B0_19") (pintype "passive"))
    )
    (net (code "51") (name "/USER_IOB0_BUFFER_IO9") (class "Default")
      (node (ref "U37") (pin "18") (pinfunction "B1_18") (pintype "passive"))
    )
    (net (code "52") (name "/USER_IOB0_BUFFER_IO10") (class "Default")
      (node (ref "U37") (pin "17") (pinfunction "B2_17") (pintype "passive"))
    )
    (net (code "53") (name "/USER_IOB0_BUFFER_IO11") (class "Default")
      (node (ref "U37") (pin "16") (pinfunction "B3_16") (pintype "passive"))
    )
    (net (code "54") (name "/USER_IOB0_BUFFER_IO12") (class "Default")
      (node (ref "U37") (pin "15") (pinfunction "B4_15") (pintype "passive"))
    )
    (net (code "55") (name "/USER_IOB0_BUFFER_IO13") (class "Default")
      (node (ref "U37") (pin "14") (pinfunction "B5_14") (pintype "passive"))
    )
    (net (code "56") (name "/USER_IOB0_BUFFER_IO14") (class "Default")
      (node (ref "U37") (pin "13") (pinfunction "B6_13") (pintype "passive"))
    )
    (net (code "57") (name "/USER_IOB0_BUFFER_IO15") (class "Default")
      (node (ref "U37") (pin "12") (pinfunction "B7_12") (pintype "passive"))
    )
    (net (code "58") (name "/USER_IOB0_BUFFER_IO16") (class "Default")
      (node (ref "U36") (pin "19") (pinfunction "B0_19") (pintype "passive"))
    )
    (net (code "59") (name "/USER_IOB0_BUFFER_IO17") (class "Default")
      (node (ref "U36") (pin "18") (pinfunction "B1_18") (pintype "passive"))
    )
    (net (code "60") (name "/USER_IOB0_BUFFER_IO18") (class "Default")
      (node (ref "U36") (pin "17") (pinfunction "B2_17") (pintype "passive"))
    )
    (net (code "61") (name "/USER_IOB0_BUFFER_IO19") (class "Default")
      (node (ref "U36") (pin "16") (pinfunction "B3_16") (pintype "passive"))
    )
    (net (code "62") (name "/USER_IOB0_BUFFER_IO20") (class "Default")
      (node (ref "U36") (pin "15") (pinfunction "B4_15") (pintype "passive"))
    )
    (net (code "63") (name "/USER_IOB0_BUFFER_IO21") (class "Default")
      (node (ref "U36") (pin "14") (pinfunction "B5_14") (pintype "passive"))
    )
    (net (code "64") (name "/USER_IOB0_BUFFER_IO22") (class "Default")
      (node (ref "U36") (pin "13") (pinfunction "B6_13") (pintype "passive"))
    )
    (net (code "65") (name "/USER_IOB0_BUFFER_IO23") (class "Default")
      (node (ref "U36") (pin "12") (pinfunction "B7_12") (pintype "passive"))
    )
    (net (code "66") (name "/USER_IOB0_BUFFER_IO24") (class "Default")
      (node (ref "U34") (pin "19") (pinfunction "B0_19") (pintype "passive"))
    )
    (net (code "67") (name "/USER_IOB0_BUFFER_IO25") (class "Default")
      (node (ref "U34") (pin "18") (pinfunction "B1_18") (pintype "passive"))
    )
    (net (code "68") (name "/USER_IOB0_BUFFER_IO26") (class "Default")
      (node (ref "U34") (pin "17") (pinfunction "B2_17") (pintype "passive"))
    )
    (net (code "69") (name "/USER_IOB0_BUFFER_IO27") (class "Default")
      (node (ref "U34") (pin "16") (pinfunction "B3_16") (pintype "passive"))
    )
    (net (code "70") (name "/USER_IOB0_BUFFER_IO28") (class "Default")
      (node (ref "U34") (pin "15") (pinfunction "B4_15") (pintype "passive"))
    )
    (net (code "71") (name "/USER_IOB0_BUFFER_IO29") (class "Default")
      (node (ref "U34") (pin "14") (pinfunction "B5_14") (pintype "passive"))
    )
    (net (code "72") (name "/USER_IOB0_BUFFER_IO30") (class "Default")
      (node (ref "U34") (pin "13") (pinfunction "B6_13") (pintype "passive"))
    )
    (net (code "73") (name "/USER_IOB0_BUFFER_IO31") (class "Default")
      (node (ref "U34") (pin "12") (pinfunction "B7_12") (pintype "passive"))
    )
    (net (code "74") (name "/USER_IOB0_BUFFER_IO32") (class "Default")
      (node (ref "U38") (pin "19") (pinfunction "B0_19") (pintype "passive"))
    )
    (net (code "75") (name "/USER_IOB0_BUFFER_IO33") (class "Default")
      (node (ref "U38") (pin "18") (pinfunction "B1_18") (pintype "passive"))
    )
    (net (code "76") (name "/USER_IOB0_BUFFER_IO34") (class "Default")
      (node (ref "U38") (pin "17") (pinfunction "B2_17") (pintype "passive"))
    )
    (net (code "77") (name "/USER_IOB0_BUFFER_IO35") (class "Default")
      (node (ref "U38") (pin "16") (pinfunction "B3_16") (pintype "passive"))
    )
    (net (code "78") (name "/USER_IOB0_BUFFER_IO36") (class "Default")
      (node (ref "U38") (pin "15") (pinfunction "B4_15") (pintype "passive"))
    )
    (net (code "79") (name "/USER_IOB0_BUFFER_IO37") (class "Default")
      (node (ref "U38") (pin "14") (pinfunction "B5_14") (pintype "passive"))
    )
    (net (code "80") (name "/USER_IOB0_BUFFER_IO38") (class "Default")
      (node (ref "U38") (pin "13") (pinfunction "B6_13") (pintype "passive"))
    )
    (net (code "81") (name "/USER_IOB0_BUFFER_IO39") (class "Default")
      (node (ref "U38") (pin "12") (pinfunction "B7_12") (pintype "passive"))
    )
    (net (code "82") (name "/USER_IOB0_BUFFER_IO40") (class "Default")
      (node (ref "U39") (pin "19") (pinfunction "B0_19") (pintype "passive"))
    )
    (net (code "83") (name "/USER_IOB0_BUFFER_IO41") (class "Default")
      (node (ref "U39") (pin "18") (pinfunction "B1_18") (pintype "passive"))
    )
    (net (code "84") (name "/USER_IOB0_BUFFER_IO42") (class "Default")
      (node (ref "U39") (pin "17") (pinfunction "B2_17") (pintype "passive"))
    )
    (net (code "85") (name "/USER_IOB0_BUFFER_IO43") (class "Default")
      (node (ref "U39") (pin "16") (pinfunction "B3_16") (pintype "passive"))
    )
    (net (code "86") (name "/USER_IOB0_BUFFER_IO44") (class "Default")
      (node (ref "U39") (pin "15") (pinfunction "B4_15") (pintype "passive"))
    )
    (net (code "87") (name "/USER_IOB0_BUFFER_IO45") (class "Default")
      (node (ref "U39") (pin "14") (pinfunction "B5_14") (pintype "passive"))
    )
    (net (code "88") (name "/USER_IOB0_BUFFER_IO46") (class "Default")
      (node (ref "U39") (pin "13") (pinfunction "B6_13") (pintype "passive"))
    )
    (net (code "89") (name "/USER_IOB0_BUFFER_IO47") (class "Default")
      (node (ref "U39") (pin "12") (pinfunction "B7_12") (pintype "passive"))
    )
    (net (code "91") (name "/USER_IOB1_BUFFER_IO0") (class "Default")
      (node (ref "U40") (pin "19") (pinfunction "B0_19") (pintype "passive"))
    )
    (net (code "92") (name "/USER_IOB1_BUFFER_IO1") (class "Default")
      (node (ref "U40") (pin "18") (pinfunction "B1_18") (pintype "passive"))
    )
    (net (code "93") (name "/USER_IOB1_BUFFER_IO2") (class "Default")
      (node (ref "U40") (pin "17") (pinfunction "B2_17") (pintype "passive"))
    )
    (net (code "94") (name "/USER_IOB1_BUFFER_IO3") (class "Default")
      (node (ref "U40") (pin "16") (pinfunction "B3_16") (pintype "passive"))
    )
    (net (code "95") (name "/USER_IOB1_BUFFER_IO4") (class "Default")
      (node (ref "U40") (pin "15") (pinfunction "B4_15") (pintype "passive"))
    )
    (net (code "96") (name "/USER_IOB1_BUFFER_IO5") (class "Default")
      (node (ref "U40") (pin "14") (pinfunction "B5_14") (pintype "passive"))
    )
    (net (code "97") (name "/USER_IOB1_BUFFER_IO6") (class "Default")
      (node (ref "U40") (pin "13") (pinfunction "B6_13") (pintype "passive"))
    )
    (net (code "98") (name "/USER_IOB1_BUFFER_IO7") (class "Default")
      (node (ref "U40") (pin "12") (pinfunction "B7_12") (pintype "passive"))
    )
    (net (code "99") (name "/USER_IOB1_BUFFER_IO8") (class "Default")
      (node (ref "U41") (pin "19") (pinfunction "B0_19") (pintype "passive"))
    )
    (net (code "100") (name "/USER_IOB1_BUFFER_IO9") (class "Default")
      (node (ref "U41") (pin "18") (pinfunction "B1_18") (pintype "passive"))
    )
    (net (code "101") (name "/USER_IOB1_BUFFER_IO10") (class "Default")
      (node (ref "U41") (pin "17") (pinfunction "B2_17") (pintype "passive"))
    )
    (net (code "102") (name "/USER_IOB1_BUFFER_IO11") (class "Default")
      (node (ref "U41") (pin "16") (pinfunction "B3_16") (pintype "passive"))
    )
    (net (code "103") (name "/USER_IOB1_BUFFER_IO12") (class "Default")
      (node (ref "U41") (pin "15") (pinfunction "B4_15") (pintype "passive"))
    )
    (net (code "104") (name "/USER_IOB1_BUFFER_IO13") (class "Default")
      (node (ref "U41") (pin "14") (pinfunction "B5_14") (pintype "passive"))
    )
    (net (code "105") (name "/USER_IOB1_BUFFER_IO14") (class "Default")
      (node (ref "U41") (pin "13") (pinfunction "B6_13") (pintype "passive"))
    )
    (net (code "106") (name "/USER_IOB1_BUFFER_IO15") (class "Default")
      (node (ref "U41") (pin "12") (pinfunction "B7_12") (pintype "passive"))
    )
    (net (code "107") (name "/USER_IOB1_BUFFER_IO16") (class "Default")
      (node (ref "U42") (pin "19") (pinfunction "B0_19") (pintype "passive"))
    )
    (net (code "108") (name "/USER_IOB1_BUFFER_IO17") (class "Default")
      (node (ref "U42") (pin "18") (pinfunction "B1_18") (pintype "passive"))
    )
    (net (code "109") (name "/USER_IOB1_BUFFER_IO18") (class "Default")
      (node (ref "U42") (pin "17") (pinfunction "B2_17") (pintype "passive"))
    )
    (net (code "110") (name "/USER_IOB1_BUFFER_IO19") (class "Default")
      (node (ref "U42") (pin "16") (pinfunction "B3_16") (pintype "passive"))
    )
    (net (code "111") (name "/USER_IOB1_BUFFER_IO20") (class "Default")
      (node (ref "U42") (pin "15") (pinfunction "B4_15") (pintype "passive"))
    )
    (net (code "112") (name "/USER_IOB1_BUFFER_IO21") (class "Default")
      (node (ref "U42") (pin "14") (pinfunction "B5_14") (pintype "passive"))
    )
    (net (code "113") (name "/USER_IOB1_BUFFER_IO22") (class "Default")
      (node (ref "U42") (pin "13") (pinfunction "B6_13") (pintype "passive"))
    )
    (net (code "114") (name "/USER_IOB1_BUFFER_IO23") (class "Default")
      (node (ref "U42") (pin "12") (pinfunction "B7_12") (pintype "passive"))
    )
    (net (code "115") (name "/USER_IOB1_BUFFER_IO24") (class "Default")
      (node (ref "U44") (pin "19") (pinfunction "B0_19") (pintype "passive"))
    )
    (net (code "116") (name "/USER_IOB1_BUFFER_IO25") (class "Default")
      (node (ref "U44") (pin "18") (pinfunction "B1_18") (pintype "passive"))
    )
    (net (code "117") (name "/USER_IOB1_BUFFER_IO26") (class "Default")
      (node (ref "U44") (pin "17") (pinfunction "B2_17") (pintype "passive"))
    )
    (net (code "118") (name "/USER_IOB1_BUFFER_IO27") (class "Default")
      (node (ref "U44") (pin "16") (pinfunction "B3_16") (pintype "passive"))
    )
    (net (code "119") (name "/USER_IOB1_BUFFER_IO28") (class "Default")
      (node (ref "U44") (pin "15") (pinfunction "B4_15") (pintype "passive"))
    )
    (net (code "120") (name "/USER_IOB1_BUFFER_IO29") (class "Default")
      (node (ref "U44") (pin "14") (pinfunction "B5_14") (pintype "passive"))
    )
    (net (code "121") (name "/USER_IOB1_BUFFER_IO30") (class "Default")
      (node (ref "U44") (pin "13") (pinfunction "B6_13") (pintype "passive"))
    )
    (net (code "122") (name "/USER_IOB1_BUFFER_IO31") (class "Default")
      (node (ref "U44") (pin "12") (pinfunction "B7_12") (pintype "passive"))
    )
    (net (code "123") (name "/USER_IOB1_BUFFER_IO32") (class "Default")
      (node (ref "U43") (pin "19") (pinfunction "B0_19") (pintype "passive"))
    )
    (net (code "124") (name "/USER_IOB1_BUFFER_IO33") (class "Default")
      (node (ref "U43") (pin "18") (pinfunction "B1_18") (pintype "passive"))
    )
    (net (code "125") (name "/USER_IOB1_BUFFER_IO34") (class "Default")
      (node (ref "U43") (pin "17") (pinfunction "B2_17") (pintype "passive"))
    )
    (net (code "126") (name "/USER_IOB1_BUFFER_IO35") (class "Default")
      (node (ref "U43") (pin "16") (pinfunction "B3_16") (pintype "passive"))
    )
    (net (code "127") (name "/USER_IOB1_BUFFER_IO36") (class "Default")
      (node (ref "U43") (pin "15") (pinfunction "B4_15") (pintype "passive"))
    )
    (net (code "128") (name "/USER_IOB1_BUFFER_IO37") (class "Default")
      (node (ref "U43") (pin "14") (pinfunction "B5_14") (pintype "passive"))
    )
    (net (code "129") (name "/USER_IOB1_BUFFER_IO38") (class "Default")
      (node (ref "U43") (pin "13") (pinfunction "B6_13") (pintype "passive"))
    )
    (net (code "130") (name "/USER_IOB1_BUFFER_IO39") (class "Default")
      (node (ref "U43") (pin "12") (pinfunction "B7_12") (pintype "passive"))
    )
    (net (code "131") (name "/USER_IOB1_BUFFER_IO40") (class "Default")
      (node (ref "U45") (pin "19") (pinfunction "B0_19") (pintype "passive"))
    )
    (net (code "132") (name "/USER_IOB1_BUFFER_IO41") (class "Default")
      (node (ref "U45") (pin "18") (pinfunction "B1_18") (pintype "passive"))
    )
    (net (code "133") (name "/USER_IOB1_BUFFER_IO42") (class "Default")
      (node (ref "U45") (pin "17") (pinfunction "B2_17") (pintype "passive"))
    )
    (net (code "134") (name "/USER_IOB1_BUFFER_IO43") (class "Default")
      (node (ref "U45") (pin "16") (pinfunction "B3_16") (pintype "passive"))
    )
    (net (code "135") (name "/USER_IOB1_BUFFER_IO44") (class "Default")
      (node (ref "U45") (pin "15") (pinfunction "B4_15") (pintype "passive"))
    )
    (net (code "136") (name "/USER_IOB1_BUFFER_IO45") (class "Default")
      (node (ref "U45") (pin "14") (pinfunction "B5_14") (pintype "passive"))
    )
    (net (code "137") (name "/USER_IOB1_BUFFER_IO46") (class "Default")
      (node (ref "U45") (pin "13") (pinfunction "B6_13") (pintype "passive"))
    )
    (net (code "138") (name "/USER_IOB1_BUFFER_IO47") (class "Default")
      (node (ref "U45") (pin "12") (pinfunction "B7_12") (pintype "passive"))
    )
    (net (code "140") (name "/USER_IO_FPGA0_IO0") (class "Default")
      (node (ref "U35") (pin "2") (pinfunction "A0_2") (pintype "passive"))
    )
    (net (code "141") (name "/USER_IO_FPGA0_IO1") (class "Default")
      (node (ref "U35") (pin "3") (pinfunction "A1_3") (pintype "passive"))
    )
    (net (code "142") (name "/USER_IO_FPGA0_IO2") (class "Default")
      (node (ref "U35") (pin "4") (pinfunction "A2_4") (pintype "passive"))
    )
    (net (code "143") (name "/USER_IO_FPGA0_IO3") (class "Default")
      (node (ref "U35") (pin "5") (pinfunction "A3_5") (pintype "passive"))
    )
    (net (code "144") (name "/USER_IO_FPGA0_IO4") (class "Default")
      (node (ref "U35") (pin "6") (pinfunction "A4_6") (pintype "passive"))
    )
    (net (code "145") (name "/USER_IO_FPGA0_IO5") (class "Default")
      (node (ref "U35") (pin "7") (pinfunction "A5_7") (pintype "passive"))
    )
    (net (code "146") (name "/USER_IO_FPGA0_IO6") (class "Default")
      (node (ref "U35") (pin "8") (pinfunction "A6_8") (pintype "passive"))
    )
    (net (code "147") (name "/USER_IO_FPGA0_IO7") (class "Default")
      (node (ref "U35") (pin "9") (pinfunction "A7_9") (pintype "passive"))
    )
    (net (code "148") (name "/USER_IO_FPGA0_IO8") (class "Default")
      (node (ref "U37") (pin "2") (pinfunction "A0_2") (pintype "passive"))
    )
    (net (code "149") (name "/USER_IO_FPGA0_IO9") (class "Default")
      (node (ref "U37") (pin "3") (pinfunction "A1_3") (pintype "passive"))
    )
    (net (code "150") (name "/USER_IO_FPGA0_IO10") (class "Default")
      (node (ref "U37") (pin "4") (pinfunction "A2_4") (pintype "passive"))
    )
    (net (code "151") (name "/USER_IO_FPGA0_IO11") (class "Default")
      (node (ref "U37") (pin "5") (pinfunction "A3_5") (pintype "passive"))
    )
    (net (code "152") (name "/USER_IO_FPGA0_IO12") (class "Default")
      (node (ref "U37") (pin "6") (pinfunction "A4_6") (pintype "passive"))
    )
    (net (code "153") (name "/USER_IO_FPGA0_IO13") (class "Default")
      (node (ref "U37") (pin "7") (pinfunction "A5_7") (pintype "passive"))
    )
    (net (code "154") (name "/USER_IO_FPGA0_IO14") (class "Default")
      (node (ref "U37") (pin "8") (pinfunction "A6_8") (pintype "passive"))
    )
    (net (code "155") (name "/USER_IO_FPGA0_IO15") (class "Default")
      (node (ref "U37") (pin "9") (pinfunction "A7_9") (pintype "passive"))
    )
    (net (code "156") (name "/USER_IO_FPGA0_IO16") (class "Default")
      (node (ref "U36") (pin "2") (pinfunction "A0_2") (pintype "passive"))
    )
    (net (code "157") (name "/USER_IO_FPGA0_IO17") (class "Default")
      (node (ref "U36") (pin "3") (pinfunction "A1_3") (pintype "passive"))
    )
    (net (code "158") (name "/USER_IO_FPGA0_IO18") (class "Default")
      (node (ref "U36") (pin "4") (pinfunction "A2_4") (pintype "passive"))
    )
    (net (code "159") (name "/USER_IO_FPGA0_IO19") (class "Default")
      (node (ref "U36") (pin "5") (pinfunction "A3_5") (pintype "passive"))
    )
    (net (code "160") (name "/USER_IO_FPGA0_IO20") (class "Default")
      (node (ref "U36") (pin "6") (pinfunction "A4_6") (pintype "passive"))
    )
    (net (code "161") (name "/USER_IO_FPGA0_IO21") (class "Default")
      (node (ref "U36") (pin "7") (pinfunction "A5_7") (pintype "passive"))
    )
    (net (code "162") (name "/USER_IO_FPGA0_IO22") (class "Default")
      (node (ref "U36") (pin "8") (pinfunction "A6_8") (pintype "passive"))
    )
    (net (code "163") (name "/USER_IO_FPGA0_IO23") (class "Default")
      (node (ref "U36") (pin "9") (pinfunction "A7_9") (pintype "passive"))
    )
    (net (code "164") (name "/USER_IO_FPGA0_IO24") (class "Default")
      (node (ref "U34") (pin "2") (pinfunction "A0_2") (pintype "passive"))
    )
    (net (code "165") (name "/USER_IO_FPGA0_IO25") (class "Default")
      (node (ref "U34") (pin "3") (pinfunction "A1_3") (pintype "passive"))
    )
    (net (code "166") (name "/USER_IO_FPGA0_IO26") (class "Default")
      (node (ref "U34") (pin "4") (pinfunction "A2_4") (pintype "passive"))
    )
    (net (code "167") (name "/USER_IO_FPGA0_IO27") (class "Default")
      (node (ref "U34") (pin "5") (pinfunction "A3_5") (pintype "passive"))
    )
    (net (code "168") (name "/USER_IO_FPGA0_IO28") (class "Default")
      (node (ref "U34") (pin "6") (pinfunction "A4_6") (pintype "passive"))
    )
    (net (code "169") (name "/USER_IO_FPGA0_IO29") (class "Default")
      (node (ref "U34") (pin "7") (pinfunction "A5_7") (pintype "passive"))
    )
    (net (code "170") (name "/USER_IO_FPGA0_IO30") (class "Default")
      (node (ref "U34") (pin "8") (pinfunction "A6_8") (pintype "passive"))
    )
    (net (code "171") (name "/USER_IO_FPGA0_IO31") (class "Default")
      (node (ref "U34") (pin "9") (pinfunction "A7_9") (pintype "passive"))
    )
    (net (code "172") (name "/USER_IO_FPGA0_IO32") (class "Default")
      (node (ref "U38") (pin "2") (pinfunction "A0_2") (pintype "passive"))
    )
    (net (code "173") (name "/USER_IO_FPGA0_IO33") (class "Default")
      (node (ref "U38") (pin "3") (pinfunction "A1_3") (pintype "passive"))
    )
    (net (code "174") (name "/USER_IO_FPGA0_IO34") (class "Default")
      (node (ref "U38") (pin "4") (pinfunction "A2_4") (pintype "passive"))
    )
    (net (code "175") (name "/USER_IO_FPGA0_IO35") (class "Default")
      (node (ref "U38") (pin "5") (pinfunction "A3_5") (pintype "passive"))
    )
    (net (code "176") (name "/USER_IO_FPGA0_IO36") (class "Default")
      (node (ref "U38") (pin "6") (pinfunction "A4_6") (pintype "passive"))
    )
    (net (code "177") (name "/USER_IO_FPGA0_IO37") (class "Default")
      (node (ref "U38") (pin "7") (pinfunction "A5_7") (pintype "passive"))
    )
    (net (code "178") (name "/USER_IO_FPGA0_IO38") (class "Default")
      (node (ref "U38") (pin "8") (pinfunction "A6_8") (pintype "passive"))
    )
    (net (code "179") (name "/USER_IO_FPGA0_IO39") (class "Default")
      (node (ref "U38") (pin "9") (pinfunction "A7_9") (pintype "passive"))
    )
    (net (code "180") (name "/USER_IO_FPGA0_IO40") (class "Default")
      (node (ref "U39") (pin "2") (pinfunction "A0_2") (pintype "passive"))
    )
    (net (code "181") (name "/USER_IO_FPGA0_IO41") (class "Default")
      (node (ref "U39") (pin "3") (pinfunction "A1_3") (pintype "passive"))
    )
    (net (code "182") (name "/USER_IO_FPGA0_IO42") (class "Default")
      (node (ref "U39") (pin "4") (pinfunction "A2_4") (pintype "passive"))
    )
    (net (code "183") (name "/USER_IO_FPGA0_IO43") (class "Default")
      (node (ref "U39") (pin "5") (pinfunction "A3_5") (pintype "passive"))
    )
    (net (code "184") (name "/USER_IO_FPGA0_IO44") (class "Default")
      (node (ref "U39") (pin "6") (pinfunction "A4_6") (pintype "passive"))
    )
    (net (code "185") (name "/USER_IO_FPGA0_IO45") (class "Default")
      (node (ref "U39") (pin "7") (pinfunction "A5_7") (pintype "passive"))
    )
    (net (code "186") (name "/USER_IO_FPGA0_IO46") (class "Default")
      (node (ref "U39") (pin "8") (pinfunction "A6_8") (pintype "passive"))
    )
    (net (code "187") (name "/USER_IO_FPGA0_IO47") (class "Default")
      (node (ref "U39") (pin "9") (pinfunction "A7_9") (pintype "passive"))
    )
    (net (code "189") (name "/USER_IO_FPGA1_IO0") (class "Default")
      (node (ref "U40") (pin "2") (pinfunction "A0_2") (pintype "passive"))
    )
    (net (code "190") (name "/USER_IO_FPGA1_IO1") (class "Default")
      (node (ref "U40") (pin "3") (pinfunction "A1_3") (pintype "passive"))
    )
    (net (code "191") (name "/USER_IO_FPGA1_IO2") (class "Default")
      (node (ref "U40") (pin "4") (pinfunction "A2_4") (pintype "passive"))
    )
    (net (code "192") (name "/USER_IO_FPGA1_IO3") (class "Default")
      (node (ref "U40") (pin "5") (pinfunction "A3_5") (pintype "passive"))
    )
    (net (code "193") (name "/USER_IO_FPGA1_IO4") (class "Default")
      (node (ref "U40") (pin "6") (pinfunction "A4_6") (pintype "passive"))
    )
    (net (code "194") (name "/USER_IO_FPGA1_IO5") (class "Default")
      (node (ref "U40") (pin "7") (pinfunction "A5_7") (pintype "passive"))
    )
    (net (code "195") (name "/USER_IO_FPGA1_IO6") (class "Default")
      (node (ref "U40") (pin "8") (pinfunction "A6_8") (pintype "passive"))
    )
    (net (code "196") (name "/USER_IO_FPGA1_IO7") (class "Default")
      (node (ref "U40") (pin "9") (pinfunction "A7_9") (pintype "passive"))
    )
    (net (code "197") (name "/USER_IO_FPGA1_IO8") (class "Default")
      (node (ref "U41") (pin "2") (pinfunction "A0_2") (pintype "passive"))
    )
    (net (code "198") (name "/USER_IO_FPGA1_IO9") (class "Default")
      (node (ref "U41") (pin "3") (pinfunction "A1_3") (pintype "passive"))
    )
    (net (code "199") (name "/USER_IO_FPGA1_IO10") (class "Default")
      (node (ref "U41") (pin "4") (pinfunction "A2_4") (pintype "passive"))
    )
    (net (code "200") (name "/USER_IO_FPGA1_IO11") (class "Default")
      (node (ref "U41") (pin "5") (pinfunction "A3_5") (pintype "passive"))
    )
    (net (code "201") (name "/USER_IO_FPGA1_IO12") (class "Default")
      (node (ref "U41") (pin "6") (pinfunction "A4_6") (pintype "passive"))
    )
    (net (code "202") (name "/USER_IO_FPGA1_IO13") (class "Default")
      (node (ref "U41") (pin "7") (pinfunction "A5_7") (pintype "passive"))
    )
    (net (code "203") (name "/USER_IO_FPGA1_IO14") (class "Default")
      (node (ref "U41") (pin "8") (pinfunction "A6_8") (pintype "passive"))
    )
    (net (code "204") (name "/USER_IO_FPGA1_IO15") (class "Default")
      (node (ref "U41") (pin "9") (pinfunction "A7_9") (pintype "passive"))
    )
    (net (code "205") (name "/USER_IO_FPGA1_IO16") (class "Default")
      (node (ref "U42") (pin "2") (pinfunction "A0_2") (pintype "passive"))
    )
    (net (code "206") (name "/USER_IO_FPGA1_IO17") (class "Default")
      (node (ref "U42") (pin "3") (pinfunction "A1_3") (pintype "passive"))
    )
    (net (code "207") (name "/USER_IO_FPGA1_IO18") (class "Default")
      (node (ref "U42") (pin "4") (pinfunction "A2_4") (pintype "passive"))
    )
    (net (code "208") (name "/USER_IO_FPGA1_IO19") (class "Default")
      (node (ref "U42") (pin "5") (pinfunction "A3_5") (pintype "passive"))
    )
    (net (code "209") (name "/USER_IO_FPGA1_IO20") (class "Default")
      (node (ref "U42") (pin "6") (pinfunction "A4_6") (pintype "passive"))
    )
    (net (code "210") (name "/USER_IO_FPGA1_IO21") (class "Default")
      (node (ref "U42") (pin "7") (pinfunction "A5_7") (pintype "passive"))
    )
    (net (code "211") (name "/USER_IO_FPGA1_IO22") (class "Default")
      (node (ref "U42") (pin "8") (pinfunction "A6_8") (pintype "passive"))
    )
    (net (code "212") (name "/USER_IO_FPGA1_IO23") (class "Default")
      (node (ref "U42") (pin "9") (pinfunction "A7_9") (pintype "passive"))
    )
    (net (code "213") (name "/USER_IO_FPGA1_IO24") (class "Default")
      (node (ref "U44") (pin "2") (pinfunction "A0_2") (pintype "passive"))
    )
    (net (code "214") (name "/USER_IO_FPGA1_IO25") (class "Default")
      (node (ref "U44") (pin "3") (pinfunction "A1_3") (pintype "passive"))
    )
    (net (code "215") (name "/USER_IO_FPGA1_IO26") (class "Default")
      (node (ref "U44") (pin "4") (pinfunction "A2_4") (pintype "passive"))
    )
    (net (code "216") (name "/USER_IO_FPGA1_IO27") (class "Default")
      (node (ref "U44") (pin "5") (pinfunction "A3_5") (pintype "passive"))
    )
    (net (code "217") (name "/USER_IO_FPGA1_IO28") (class "Default")
      (node (ref "U44") (pin "6") (pinfunction "A4_6") (pintype "passive"))
    )
    (net (code "218") (name "/USER_IO_FPGA1_IO29") (class "Default")
      (node (ref "U44") (pin "7") (pinfunction "A5_7") (pintype "passive"))
    )
    (net (code "219") (name "/USER_IO_FPGA1_IO30") (class "Default")
      (node (ref "U44") (pin "8") (pinfunction "A6_8") (pintype "passive"))
    )
    (net (code "220") (name "/USER_IO_FPGA1_IO31") (class "Default")
      (node (ref "U44") (pin "9") (pinfunction "A7_9") (pintype "passive"))
    )
    (net (code "221") (name "/USER_IO_FPGA1_IO32") (class "Default")
      (node (ref "U43") (pin "2") (pinfunction "A0_2") (pintype "passive"))
    )
    (net (code "222") (name "/USER_IO_FPGA1_IO33") (class "Default")
      (node (ref "U43") (pin "3") (pinfunction "A1_3") (pintype "passive"))
    )
    (net (code "223") (name "/USER_IO_FPGA1_IO34") (class "Default")
      (node (ref "U43") (pin "4") (pinfunction "A2_4") (pintype "passive"))
    )
    (net (code "224") (name "/USER_IO_FPGA1_IO35") (class "Default")
      (node (ref "U43") (pin "5") (pinfunction "A3_5") (pintype "passive"))
    )
    (net (code "225") (name "/USER_IO_FPGA1_IO36") (class "Default")
      (node (ref "U43") (pin "6") (pinfunction "A4_6") (pintype "passive"))
    )
    (net (code "226") (name "/USER_IO_FPGA1_IO37") (class "Default")
      (node (ref "U43") (pin "7") (pinfunction "A5_7") (pintype "passive"))
    )
    (net (code "227") (name "/USER_IO_FPGA1_IO38") (class "Default")
      (node (ref "U43") (pin "8") (pinfunction "A6_8") (pintype "passive"))
    )
    (net (code "228") (name "/USER_IO_FPGA1_IO39") (class "Default")
      (node (ref "U43") (pin "9") (pinfunction "A7_9") (pintype "passive"))
    )
    (net (code "229") (name "/USER_IO_FPGA1_IO40") (class "Default")
      (node (ref "U45") (pin "2") (pinfunction "A0_2") (pintype "passive"))
    )
    (net (code "230") (name "/USER_IO_FPGA1_IO41") (class "Default")
      (node (ref "U45") (pin "3") (pinfunction "A1_3") (pintype "passive"))
    )
    (net (code "231") (name "/USER_IO_FPGA1_IO42") (class "Default")
      (node (ref "U45") (pin "4") (pinfunction "A2_4") (pintype "passive"))
    )
    (net (code "232") (name "/USER_IO_FPGA1_IO43") (class "Default")
      (node (ref "U45") (pin "5") (pinfunction "A3_5") (pintype "passive"))
    )
    (net (code "233") (name "/USER_IO_FPGA1_IO44") (class "Default")
      (node (ref "U45") (pin "6") (pinfunction "A4_6") (pintype "passive"))
    )
    (net (code "234") (name "/USER_IO_FPGA1_IO45") (class "Default")
      (node (ref "U45") (pin "7") (pinfunction "A5_7") (pintype "passive"))
    )
    (net (code "235") (name "/USER_IO_FPGA1_IO46") (class "Default")
      (node (ref "U45") (pin "8") (pinfunction "A6_8") (pintype "passive"))
    )
    (net (code "236") (name "/USER_IO_FPGA1_IO47") (class "Default")
      (node (ref "U45") (pin "9") (pinfunction "A7_9") (pintype "passive"))
    )
    (net (code "238") (name "/USER_PMOD0_FPGA0_LVIO0") (class "Default")
      (node (ref "U46") (pin "2") (pinfunction "A0_2") (pintype "passive"))
    )
    (net (code "239") (name "/USER_PMOD0_FPGA0_LVIO1") (class "Default")
      (node (ref "U46") (pin "3") (pinfunction "A1_3") (pintype "passive"))
    )
    (net (code "240") (name "/USER_PMOD0_FPGA0_LVIO2") (class "Default")
      (node (ref "U46") (pin "4") (pinfunction "A2_4") (pintype "passive"))
    )
    (net (code "241") (name "/USER_PMOD0_FPGA0_LVIO3") (class "Default")
      (node (ref "U46") (pin "5") (pinfunction "A3_5") (pintype "passive"))
    )
    (net (code "242") (name "/USER_PMOD0_FPGA0_LVIO4") (class "Default")
      (node (ref "U46") (pin "6") (pinfunction "A4_6") (pintype "passive"))
    )
    (net (code "243") (name "/USER_PMOD0_FPGA0_LVIO5") (class "Default")
      (node (ref "U46") (pin "7") (pinfunction "A5_7") (pintype "passive"))
    )
    (net (code "244") (name "/USER_PMOD0_FPGA0_LVIO6") (class "Default")
      (node (ref "U46") (pin "8") (pinfunction "A6_8") (pintype "passive"))
    )
    (net (code "245") (name "/USER_PMOD0_FPGA0_LVIO7") (class "Default")
      (node (ref "U46") (pin "9") (pinfunction "A7_9") (pintype "passive"))
    )
    (net (code "247") (name "/USER_PMOD1_FPGA0_LVIO0") (class "Default")
      (node (ref "U47") (pin "2") (pinfunction "A0_2") (pintype "passive"))
    )
    (net (code "248") (name "/USER_PMOD1_FPGA0_LVIO1") (class "Default")
      (node (ref "U47") (pin "3") (pinfunction "A1_3") (pintype "passive"))
    )
    (net (code "249") (name "/USER_PMOD1_FPGA0_LVIO2") (class "Default")
      (node (ref "U47") (pin "4") (pinfunction "A2_4") (pintype "passive"))
    )
    (net (code "250") (name "/USER_PMOD1_FPGA0_LVIO3") (class "Default")
      (node (ref "U47") (pin "5") (pinfunction "A3_5") (pintype "passive"))
    )
    (net (code "251") (name "/USER_PMOD1_FPGA0_LVIO4") (class "Default")
      (node (ref "U47") (pin "6") (pinfunction "A4_6") (pintype "passive"))
    )
    (net (code "252") (name "/USER_PMOD1_FPGA0_LVIO5") (class "Default")
      (node (ref "U47") (pin "7") (pinfunction "A5_7") (pintype "passive"))
    )
    (net (code "253") (name "/USER_PMOD1_FPGA0_LVIO6") (class "Default")
      (node (ref "U47") (pin "8") (pinfunction "A6_8") (pintype "passive"))
    )
    (net (code "254") (name "/USER_PMOD1_FPGA0_LVIO7") (class "Default")
      (node (ref "U47") (pin "9") (pinfunction "A7_9") (pintype "passive"))
    )
    (net (code "256") (name "/USER_PMOD2_FPGA0_LVIO0") (class "Default")
      (node (ref "U48") (pin "2") (pinfunction "A0_2") (pintype "passive"))
    )
    (net (code "257") (name "/USER_PMOD2_FPGA0_LVIO1") (class "Default")
      (node (ref "U48") (pin "3") (pinfunction "A1_3") (pintype "passive"))
    )
    (net (code "258") (name "/USER_PMOD2_FPGA0_LVIO2") (class "Default")
      (node (ref "U48") (pin "4") (pinfunction "A2_4") (pintype "passive"))
    )
    (net (code "259") (name "/USER_PMOD2_FPGA0_LVIO3") (class "Default")
      (node (ref "U48") (pin "5") (pinfunction "A3_5") (pintype "passive"))
    )
    (net (code "260") (name "/USER_PMOD2_FPGA0_LVIO4") (class "Default")
      (node (ref "U48") (pin "6") (pinfunction "A4_6") (pintype "passive"))
    )
    (net (code "261") (name "/USER_PMOD2_FPGA0_LVIO5") (class "Default")
      (node (ref "U48") (pin "7") (pinfunction "A5_7") (pintype "passive"))
    )
    (net (code "262") (name "/USER_PMOD2_FPGA0_LVIO6") (class "Default")
      (node (ref "U48") (pin "8") (pinfunction "A6_8") (pintype "passive"))
    )
    (net (code "263") (name "/USER_PMOD2_FPGA0_LVIO7") (class "Default")
      (node (ref "U48") (pin "9") (pinfunction "A7_9") (pintype "passive"))
    )
    (net (code "265") (name "/USER_PMOD3_FPGA0_LVIO0") (class "Default")
      (node (ref "U49") (pin "2") (pinfunction "A0_2") (pintype "passive"))
    )
    (net (code "266") (name "/USER_PMOD3_FPGA0_LVIO1") (class "Default")
      (node (ref "U49") (pin "3") (pinfunction "A1_3") (pintype "passive"))
    )
    (net (code "267") (name "/USER_PMOD3_FPGA0_LVIO2") (class "Default")
      (node (ref "U49") (pin "4") (pinfunction "A2_4") (pintype "passive"))
    )
    (net (code "268") (name "/USER_PMOD3_FPGA0_LVIO3") (class "Default")
      (node (ref "U49") (pin "5") (pinfunction "A3_5") (pintype "passive"))
    )
    (net (code "269") (name "/USER_PMOD3_FPGA0_LVIO4") (class "Default")
      (node (ref "U49") (pin "6") (pinfunction "A4_6") (pintype "passive"))
    )
    (net (code "270") (name "/USER_PMOD3_FPGA0_LVIO5") (class "Default")
      (node (ref "U49") (pin "7") (pinfunction "A5_7") (pintype "passive"))
    )
    (net (code "271") (name "/USER_PMOD3_FPGA0_LVIO6") (class "Default")
      (node (ref "U49") (pin "8") (pinfunction "A6_8") (pintype "passive"))
    )
    (net (code "272") (name "/USER_PMOD3_FPGA0_LVIO7") (class "Default")
      (node (ref "U49") (pin "9") (pinfunction "A7_9") (pintype "passive"))
    )
    (net (code "274") (name "GND") (class "Default")
      (node (ref "C308") (pin "1") (pinfunction "1_1") (pintype "passive"))
      (node (ref "C309") (pin "1") (pinfunction "1_1") (pintype "passive"))
      (node (ref "C310") (pin "1") (pinfunction "1_1") (pintype "passive"))
      (node (ref "C311") (pin "1") (pinfunction "1_1") (pintype "passive"))
      (node (ref "C312") (pin "1") (pinfunction "1_1") (pintype "passive"))
      (node (ref "C313") (pin "1") (pinfunction "1_1") (pintype "passive"))
      (node (ref "C314") (pin "1") (pinfunction "1_1") (pintype "passive"))
      (node (ref "C315") (pin "1") (pinfunction "1_1") (pintype "passive"))
      (node (ref "C316") (pin "1") (pinfunction "1_1") (pintype "passive"))
      (node (ref "C317") (pin "1") (pinfunction "1_1") (pintype "passive"))
      (node (ref "C318") (pin "1") (pinfunction "1_1") (pintype "passive"))
      (node (ref "C319") (pin "1") (pinfunction "1_1") (pintype "passive"))
      (node (ref "C320") (pin "1") (pinfunction "1_1") (pintype "passive"))
      (node (ref "C321") (pin "1") (pinfunction "1_1") (pintype "passive"))
      (node (ref "C322") (pin "1") (pinfunction "1_1") (pintype "passive"))
      (node (ref "C323") (pin "1") (pinfunction "1_1") (pintype "passive"))
      (node (ref "C324") (pin "1") (pinfunction "1_1") (pintype "passive"))
      (node (ref "C325") (pin "1") (pinfunction "1_1") (pintype "passive"))
      (node (ref "C326") (pin "1") (pinfunction "1_1") (pintype "passive"))
      (node (ref "C327") (pin "1") (pinfunction "1_1") (pintype "passive"))
      (node (ref "C328") (pin "1") (pinfunction "1_1") (pintype "passive"))
      (node (ref "C329") (pin "1") (pinfunction "1_1") (pintype "passive"))
      (node (ref "C330") (pin "1") (pinfunction "1_1") (pintype "passive"))
      (node (ref "C331") (pin "1") (pinfunction "1_1") (pintype "passive"))
      (node (ref "C332") (pin "1") (pinfunction "1_1") (pintype "passive"))
      (node (ref "C333") (pin "1") (pinfunction "1_1") (pintype "passive"))
      (node (ref "C334") (pin "1") (pinfunction "1_1") (pintype "passive"))
      (node (ref "C335") (pin "1") (pinfunction "1_1") (pintype "passive"))
      (node (ref "C336") (pin "1") (pinfunction "1_1") (pintype "passive"))
      (node (ref "C337") (pin "1") (pinfunction "1_1") (pintype "passive"))
      (node (ref "C338") (pin "1") (pinfunction "1_1") (pintype "passive"))
      (node (ref "C339") (pin "1") (pinfunction "1_1") (pintype "passive"))
      (node (ref "C340") (pin "1") (pinfunction "1_1") (pintype "passive"))
      (node (ref "C341") (pin "1") (pinfunction "1_1") (pintype "passive"))
      (node (ref "Q21") (pin "2") (pinfunction "S_2") (pintype "passive"))
      (node (ref "Q22") (pin "2") (pinfunction "S_2") (pintype "passive"))
      (node (ref "R277") (pin "2") (pinfunction "2_2") (pintype "passive"))
      (node (ref "R278") (pin "2") (pinfunction "2_2") (pintype "passive"))
      (node (ref "U34") (pin "10") (pinfunction "GND_10") (pintype "passive"))
      (node (ref "U35") (pin "10") (pinfunction "GND_10") (pintype "passive"))
      (node (ref "U36") (pin "10") (pinfunction "GND_10") (pintype "passive"))
      (node (ref "U37") (pin "10") (pinfunction "GND_10") (pintype "passive"))
      (node (ref "U38") (pin "10") (pinfunction "GND_10") (pintype "passive"))
      (node (ref "U39") (pin "10") (pinfunction "GND_10") (pintype "passive"))
      (node (ref "U40") (pin "10") (pinfunction "GND_10") (pintype "passive"))
      (node (ref "U41") (pin "10") (pinfunction "GND_10") (pintype "passive"))
      (node (ref "U42") (pin "10") (pinfunction "GND_10") (pintype "passive"))
      (node (ref "U43") (pin "10") (pinfunction "GND_10") (pintype "passive"))
      (node (ref "U44") (pin "10") (pinfunction "GND_10") (pintype "passive"))
      (node (ref "U45") (pin "10") (pinfunction "GND_10") (pintype "passive"))
      (node (ref "U46") (pin "10") (pinfunction "GND_10") (pintype "passive"))
      (node (ref "U47") (pin "10") (pinfunction "GND_10") (pintype "passive"))
      (node (ref "U48") (pin "10") (pinfunction "GND_10") (pintype "passive"))
      (node (ref "U49") (pin "10") (pinfunction "GND_10") (pintype "passive"))
    )
    (net (code "275") (name "Net-(Q21-G)") (class "Default")
      (node (ref "C340") (pin "2") (pinfunction "2_2") (pintype "passive"))
      (node (ref "Q21") (pin "1") (pinfunction "G_1") (pintype "passive"))
      (node (ref "R275") (pin "1") (pinfunction "1_1") (pintype "passive"))
    )
    (net (code "276") (name "Net-(Q22-G)") (class "Default")
      (node (ref "C341") (pin "2") (pinfunction "2_2") (pintype "passive"))
      (node (ref "Q22") (pin "1") (pinfunction "G_1") (pintype "passive"))
      (node (ref "R276") (pin "1") (pinfunction "1_1") (pintype "passive"))
    )
    (net (code "277") (name "unconnected-(U34-EP-Pad21)") (class "Default")
      (node (ref "U34") (pin "21") (pinfunction "EP_21") (pintype "passive+no_connect"))
    )
    (net (code "278") (name "unconnected-(U35-EP-Pad21)") (class "Default")
      (node (ref "U35") (pin "21") (pinfunction "EP_21") (pintype "passive+no_connect"))
    )
    (net (code "279") (name "unconnected-(U36-EP-Pad21)") (class "Default")
      (node (ref "U36") (pin "21") (pinfunction "EP_21") (pintype "passive+no_connect"))
    )
    (net (code "280") (name "unconnected-(U37-EP-Pad21)") (class "Default")
      (node (ref "U37") (pin "21") (pinfunction "EP_21") (pintype "passive+no_connect"))
    )
    (net (code "281") (name "unconnected-(U38-EP-Pad21)") (class "Default")
      (node (ref "U38") (pin "21") (pinfunction "EP_21") (pintype "passive+no_connect"))
    )
    (net (code "282") (name "unconnected-(U39-EP-Pad21)") (class "Default")
      (node (ref "U39") (pin "21") (pinfunction "EP_21") (pintype "passive+no_connect"))
    )
    (net (code "283") (name "unconnected-(U40-EP-Pad21)") (class "Default")
      (node (ref "U40") (pin "21") (pinfunction "EP_21") (pintype "passive+no_connect"))
    )
    (net (code "284") (name "unconnected-(U41-EP-Pad21)") (class "Default")
      (node (ref "U41") (pin "21") (pinfunction "EP_21") (pintype "passive+no_connect"))
    )
    (net (code "285") (name "unconnected-(U42-EP-Pad21)") (class "Default")
      (node (ref "U42") (pin "21") (pinfunction "EP_21") (pintype "passive+no_connect"))
    )
    (net (code "286") (name "unconnected-(U43-EP-Pad21)") (class "Default")
      (node (ref "U43") (pin "21") (pinfunction "EP_21") (pintype "passive+no_connect"))
    )
    (net (code "287") (name "unconnected-(U44-EP-Pad21)") (class "Default")
      (node (ref "U44") (pin "21") (pinfunction "EP_21") (pintype "passive+no_connect"))
    )
    (net (code "288") (name "unconnected-(U45-EP-Pad21)") (class "Default")
      (node (ref "U45") (pin "21") (pinfunction "EP_21") (pintype "passive+no_connect"))
    )
    (net (code "289") (name "unconnected-(U46-EP-Pad21)") (class "Default")
      (node (ref "U46") (pin "21") (pinfunction "EP_21") (pintype "passive+no_connect"))
    )
    (net (code "290") (name "unconnected-(U47-EP-Pad21)") (class "Default")
      (node (ref "U47") (pin "21") (pinfunction "EP_21") (pintype "passive+no_connect"))
    )
    (net (code "291") (name "unconnected-(U48-EP-Pad21)") (class "Default")
      (node (ref "U48") (pin "21") (pinfunction "EP_21") (pintype "passive+no_connect"))
    )
    (net (code "292") (name "unconnected-(U49-EP-Pad21)") (class "Default")
      (node (ref "U49") (pin "21") (pinfunction "EP_21") (pintype "passive+no_connect"))
    )
  )
)
